# SupplyBox.net
KiCad netlist of a schematic drawn in Altium Designer
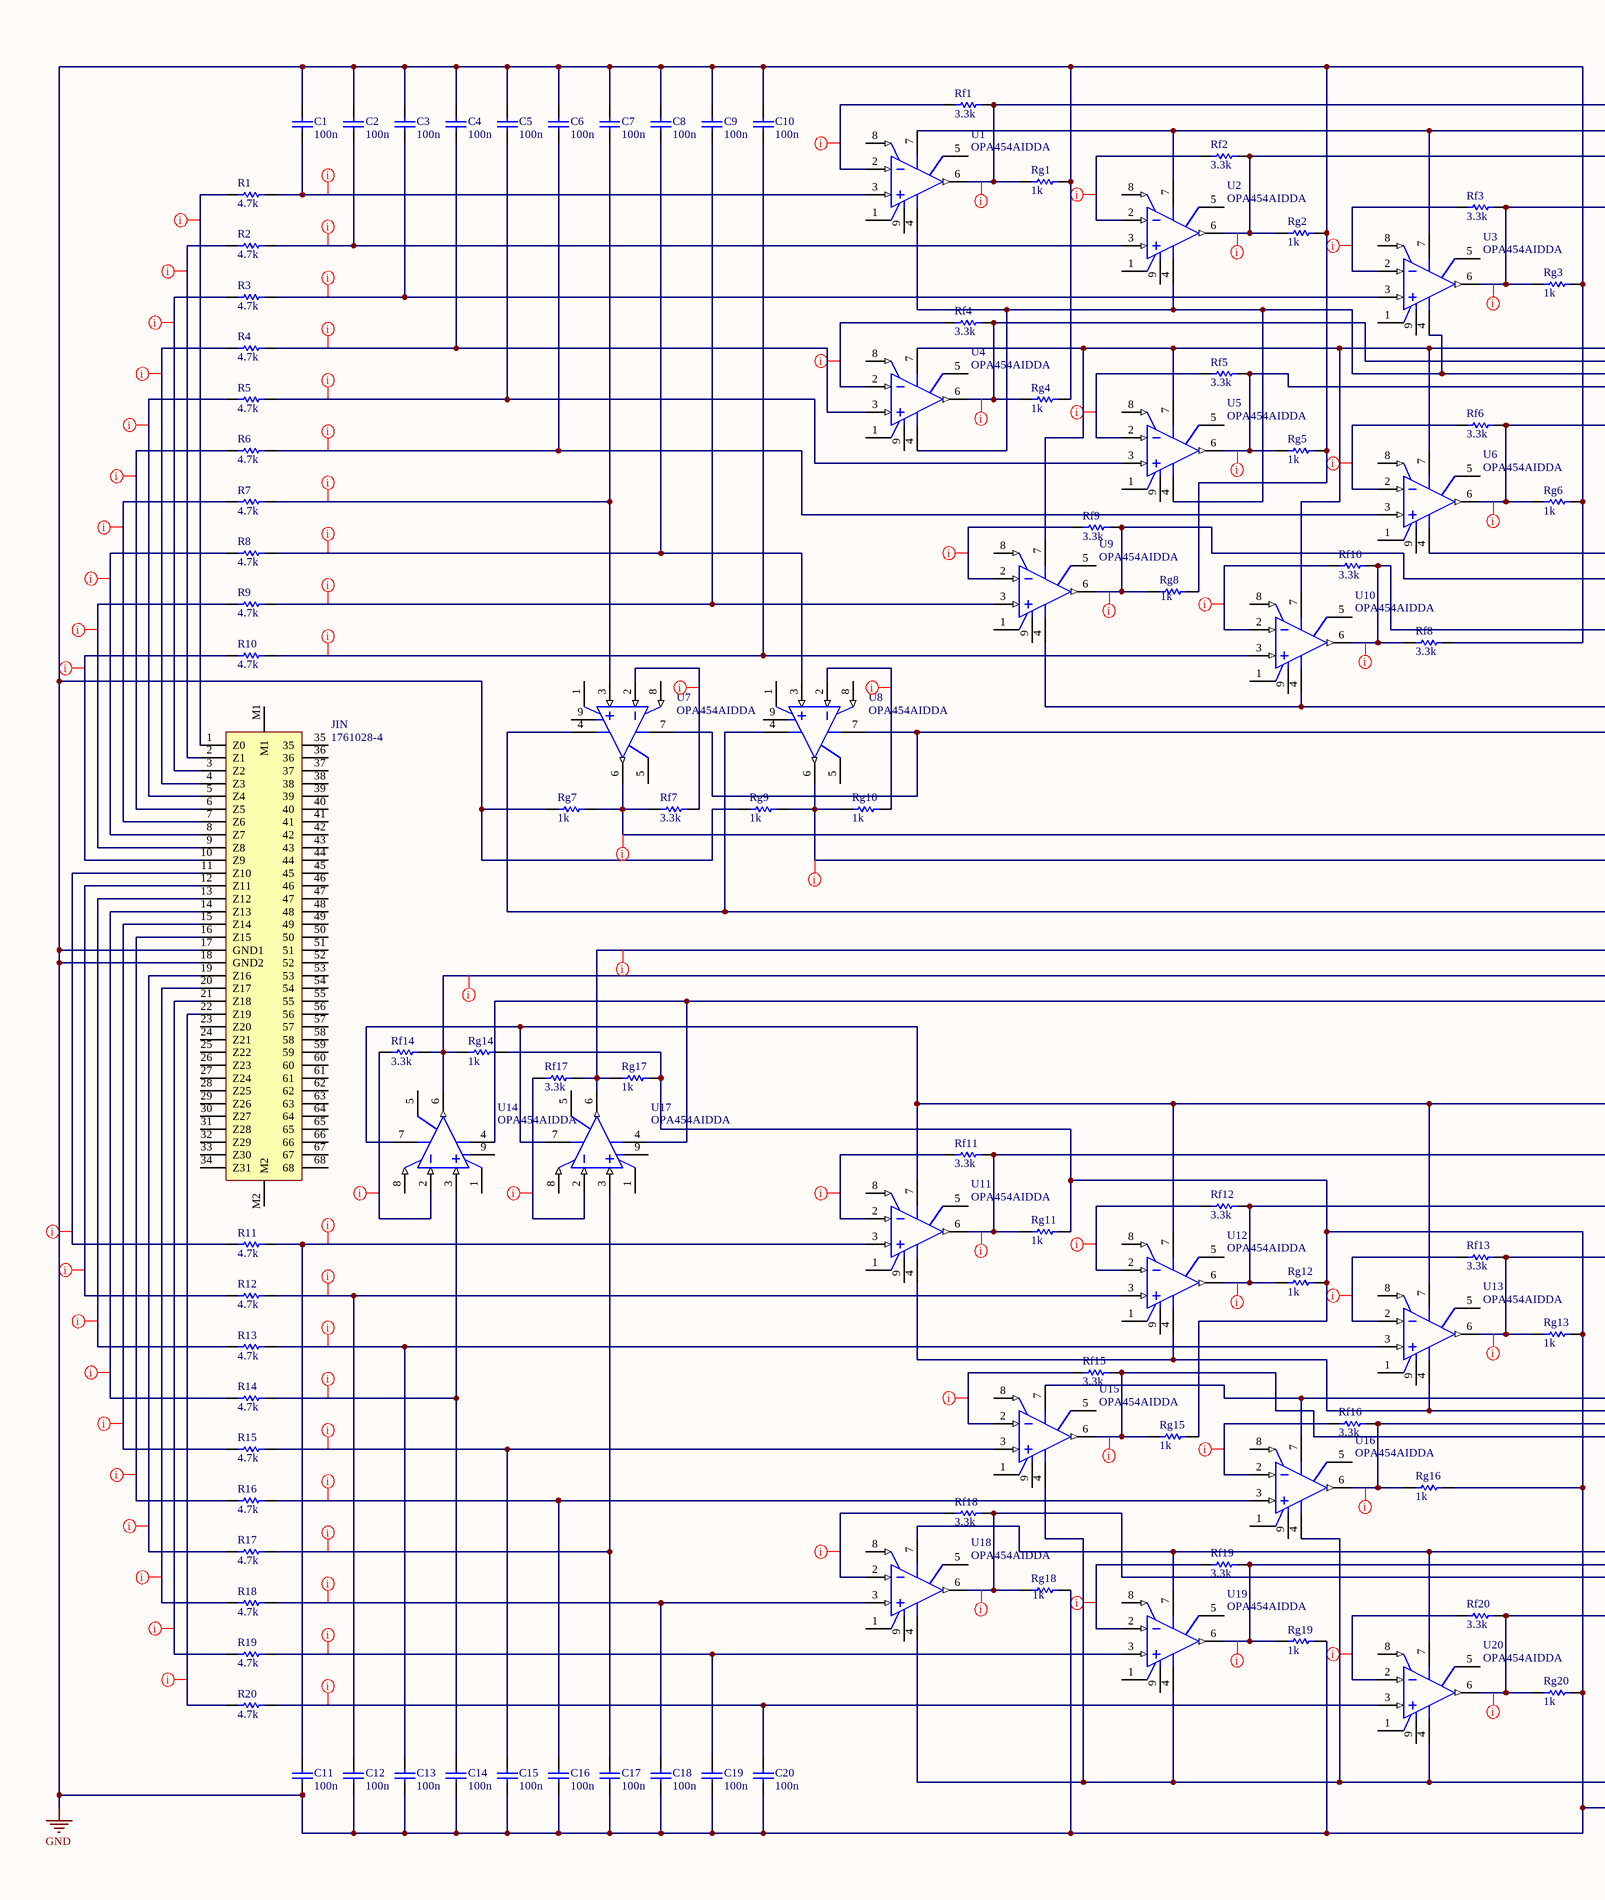
[diagram p0: SupplyBox.SchDoc, left]
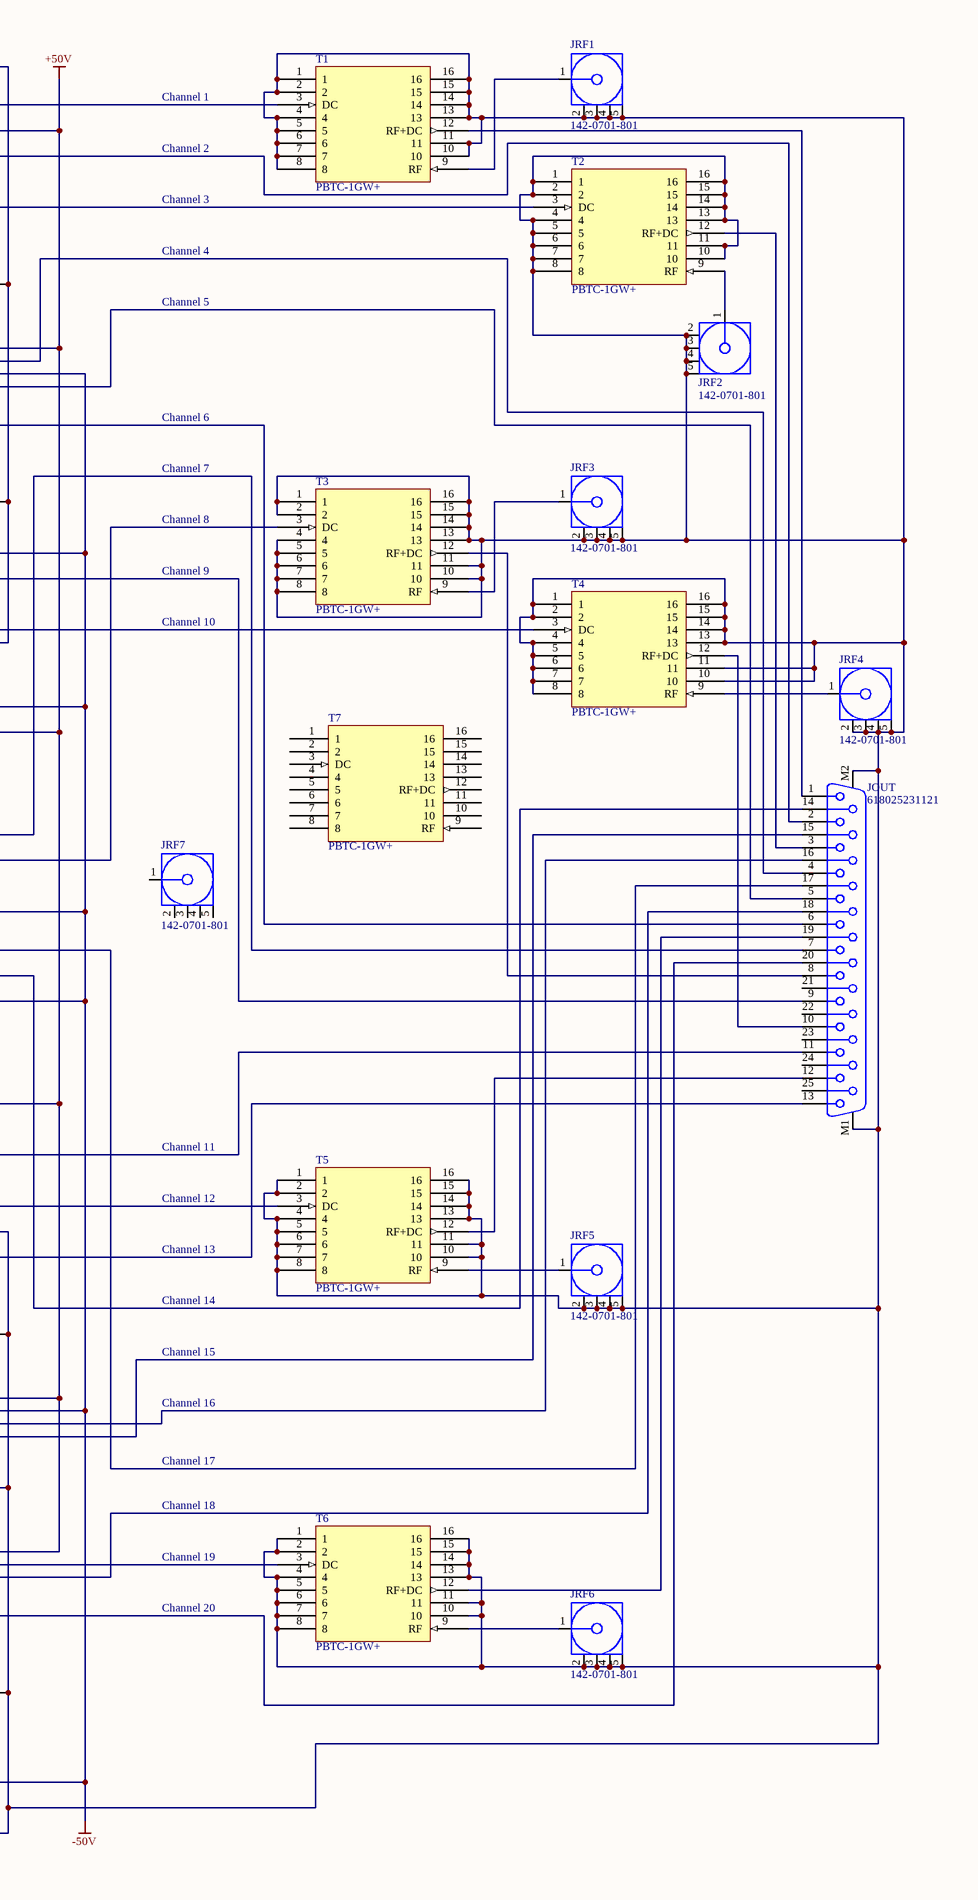
[diagram p1: SupplyBox.SchDoc, right]

(export (version "E")
  (design (tool "Eeschema 10.0.6"))
  (components
    (comp (ref "C1")
      (value "100n")
      (footprint "CAPC2013X145X48NL20T23")
      (fields (field (name "MANUFACTURER") "Vitramon") (field (name "PART NUMBER") "VJ0805Y104KNAAT"))
      (libsource (lib "Altium Content Vault") (part "CAP"))
    )
    (comp (ref "C2")
      (value "100n")
      (footprint "CAPC2013X145X48NL20T23")
      (fields (field (name "MANUFACTURER") "Vitramon") (field (name "PART NUMBER") "VJ0805Y104KNAAT"))
      (libsource (lib "Altium Content Vault") (part "CAP"))
    )
    (comp (ref "C3")
      (value "100n")
      (footprint "CAPC2013X145X48NL20T23")
      (fields (field (name "MANUFACTURER") "Vitramon") (field (name "PART NUMBER") "VJ0805Y104KNAAT"))
      (libsource (lib "Altium Content Vault") (part "CAP"))
    )
    (comp (ref "C4")
      (value "100n")
      (footprint "CAPC2013X145X48NL20T23")
      (fields (field (name "MANUFACTURER") "Vitramon") (field (name "PART NUMBER") "VJ0805Y104KNAAT"))
      (libsource (lib "Altium Content Vault") (part "CAP"))
    )
    (comp (ref "C5")
      (value "100n")
      (footprint "CAPC2013X145X48NL20T23")
      (fields (field (name "MANUFACTURER") "Vitramon") (field (name "PART NUMBER") "VJ0805Y104KNAAT"))
      (libsource (lib "Altium Content Vault") (part "CAP"))
    )
    (comp (ref "C6")
      (value "100n")
      (footprint "CAPC2013X145X48NL20T23")
      (fields (field (name "MANUFACTURER") "Vitramon") (field (name "PART NUMBER") "VJ0805Y104KNAAT"))
      (libsource (lib "Altium Content Vault") (part "CAP"))
    )
    (comp (ref "C7")
      (value "100n")
      (footprint "CAPC2013X145X48NL20T23")
      (fields (field (name "MANUFACTURER") "Vitramon") (field (name "PART NUMBER") "VJ0805Y104KNAAT"))
      (libsource (lib "Altium Content Vault") (part "CAP"))
    )
    (comp (ref "C8")
      (value "100n")
      (footprint "CAPC2013X145X48NL20T23")
      (fields (field (name "MANUFACTURER") "Vitramon") (field (name "PART NUMBER") "VJ0805Y104KNAAT"))
      (libsource (lib "Altium Content Vault") (part "CAP"))
    )
    (comp (ref "C9")
      (value "100n")
      (footprint "CAPC2013X145X48NL20T23")
      (fields (field (name "MANUFACTURER") "Vitramon") (field (name "PART NUMBER") "VJ0805Y104KNAAT"))
      (libsource (lib "Altium Content Vault") (part "CAP"))
    )
    (comp (ref "C10")
      (value "100n")
      (footprint "CAPC2013X145X48NL20T23")
      (fields (field (name "MANUFACTURER") "Vitramon") (field (name "PART NUMBER") "VJ0805Y104KNAAT"))
      (libsource (lib "Altium Content Vault") (part "CAP"))
    )
    (comp (ref "C11")
      (value "100n")
      (footprint "CAPC2013X145X48NL20T23")
      (fields (field (name "MANUFACTURER") "Vitramon") (field (name "PART NUMBER") "VJ0805Y104KNAAT"))
      (libsource (lib "Altium Content Vault") (part "CAP"))
    )
    (comp (ref "C12")
      (value "100n")
      (footprint "CAPC2013X145X48NL20T23")
      (fields (field (name "MANUFACTURER") "Vitramon") (field (name "PART NUMBER") "VJ0805Y104KNAAT"))
      (libsource (lib "Altium Content Vault") (part "CAP"))
    )
    (comp (ref "C13")
      (value "100n")
      (footprint "CAPC2013X145X48NL20T23")
      (fields (field (name "MANUFACTURER") "Vitramon") (field (name "PART NUMBER") "VJ0805Y104KNAAT"))
      (libsource (lib "Altium Content Vault") (part "CAP"))
    )
    (comp (ref "C14")
      (value "100n")
      (footprint "CAPC2013X145X48NL20T23")
      (fields (field (name "MANUFACTURER") "Vitramon") (field (name "PART NUMBER") "VJ0805Y104KNAAT"))
      (libsource (lib "Altium Content Vault") (part "CAP"))
    )
    (comp (ref "C15")
      (value "100n")
      (footprint "CAPC2013X145X48NL20T23")
      (fields (field (name "MANUFACTURER") "Vitramon") (field (name "PART NUMBER") "VJ0805Y104KNAAT"))
      (libsource (lib "Altium Content Vault") (part "CAP"))
    )
    (comp (ref "C16")
      (value "100n")
      (footprint "CAPC2013X145X48NL20T23")
      (fields (field (name "MANUFACTURER") "Vitramon") (field (name "PART NUMBER") "VJ0805Y104KNAAT"))
      (libsource (lib "Altium Content Vault") (part "CAP"))
    )
    (comp (ref "C17")
      (value "100n")
      (footprint "CAPC2013X145X48NL20T23")
      (fields (field (name "MANUFACTURER") "Vitramon") (field (name "PART NUMBER") "VJ0805Y104KNAAT"))
      (libsource (lib "Altium Content Vault") (part "CAP"))
    )
    (comp (ref "C18")
      (value "100n")
      (footprint "CAPC2013X145X48NL20T23")
      (fields (field (name "MANUFACTURER") "Vitramon") (field (name "PART NUMBER") "VJ0805Y104KNAAT"))
      (libsource (lib "Altium Content Vault") (part "CAP"))
    )
    (comp (ref "C19")
      (value "100n")
      (footprint "CAPC2013X145X48NL20T23")
      (fields (field (name "MANUFACTURER") "Vitramon") (field (name "PART NUMBER") "VJ0805Y104KNAAT"))
      (libsource (lib "Altium Content Vault") (part "CAP"))
    )
    (comp (ref "C20")
      (value "100n")
      (footprint "CAPC2013X145X48NL20T23")
      (fields (field (name "MANUFACTURER") "Vitramon") (field (name "PART NUMBER") "VJ0805Y104KNAAT"))
      (libsource (lib "Altium Content Vault") (part "CAP"))
    )
    (comp (ref "JIN")
      (value "1761028-4")
      (footprint "1761028-4-Footprint-1")
      (libsource (lib "Li-Ren Liu") (part "1761028-4-Symbol-1"))
    )
    (comp (ref "JOUT")
      (value "618025231121")
      (footprint "618025231121")
      (libsource (lib "Altium Content Vault") (part "D-Sub_Female_25p"))
    )
    (comp (ref "JRF1")
      (value "142-0701-801")
      (footprint "CINC-142-0701-801_V")
      (description "SMA End Launch Jack Receptacle, 50 Ohm, 0 to 18 GHz, -65 to 165 degC, 5-Pin SMD, RoHS, Bulk")
      (fields (field (name "MANUFACTURER") "EmersonConnectivitySolutions"))
      (libsource (lib "Altium Content Vault") (part "CN-S-4F-RF5"))
    )
    (comp (ref "JRF2")
      (value "142-0701-801")
      (footprint "CINC-142-0701-801_V")
      (description "SMA End Launch Jack Receptacle, 50 Ohm, 0 to 18 GHz, -65 to 165 degC, 5-Pin SMD, RoHS, Bulk")
      (fields (field (name "MANUFACTURER") "EmersonConnectivitySolutions"))
      (libsource (lib "Altium Content Vault") (part "CN-S-4F-RF5"))
    )
    (comp (ref "JRF3")
      (value "142-0701-801")
      (footprint "CINC-142-0701-801_V")
      (description "SMA End Launch Jack Receptacle, 50 Ohm, 0 to 18 GHz, -65 to 165 degC, 5-Pin SMD, RoHS, Bulk")
      (fields (field (name "MANUFACTURER") "EmersonConnectivitySolutions"))
      (libsource (lib "Altium Content Vault") (part "CN-S-4F-RF5"))
    )
    (comp (ref "JRF4")
      (value "142-0701-801")
      (footprint "CINC-142-0701-801_V")
      (description "SMA End Launch Jack Receptacle, 50 Ohm, 0 to 18 GHz, -65 to 165 degC, 5-Pin SMD, RoHS, Bulk")
      (fields (field (name "MANUFACTURER") "EmersonConnectivitySolutions"))
      (libsource (lib "Altium Content Vault") (part "CN-S-4F-RF5"))
    )
    (comp (ref "JRF5")
      (value "142-0701-801")
      (footprint "CINC-142-0701-801_V")
      (description "SMA End Launch Jack Receptacle, 50 Ohm, 0 to 18 GHz, -65 to 165 degC, 5-Pin SMD, RoHS, Bulk")
      (fields (field (name "MANUFACTURER") "EmersonConnectivitySolutions"))
      (libsource (lib "Altium Content Vault") (part "CN-S-4F-RF5"))
    )
    (comp (ref "JRF6")
      (value "142-0701-801")
      (footprint "CINC-142-0701-801_V")
      (description "SMA End Launch Jack Receptacle, 50 Ohm, 0 to 18 GHz, -65 to 165 degC, 5-Pin SMD, RoHS, Bulk")
      (fields (field (name "MANUFACTURER") "EmersonConnectivitySolutions"))
      (libsource (lib "Altium Content Vault") (part "CN-S-4F-RF5"))
    )
    (comp (ref "JRF7")
      (value "142-0701-801")
      (footprint "CINC-142-0701-801_V")
      (description "SMA End Launch Jack Receptacle, 50 Ohm, 0 to 18 GHz, -65 to 165 degC, 5-Pin SMD, RoHS, Bulk")
      (fields (field (name "MANUFACTURER") "EmersonConnectivitySolutions"))
      (libsource (lib "Altium Content Vault") (part "CN-S-4F-RF5"))
    )
    (comp (ref "R1")
      (value "4.7k")
      (footprint "RESC2013X60X35NL10T20")
      (description "Chip Resistor, 47 KOhm, +/- 1%, 0.125 W, -55 to 155 degC, 0805 (2012 Metric), RoHS, Tape and Reel")
      (fields (field (name "MANUFACTURER") "Yageo"))
      (libsource (lib "Altium Content Vault") (part "RES-2"))
    )
    (comp (ref "R2")
      (value "4.7k")
      (footprint "RESC2013X60X35NL10T20")
      (description "Chip Resistor, 47 KOhm, +/- 1%, 0.125 W, -55 to 155 degC, 0805 (2012 Metric), RoHS, Tape and Reel")
      (fields (field (name "MANUFACTURER") "Yageo"))
      (libsource (lib "Altium Content Vault") (part "RES-2"))
    )
    (comp (ref "R3")
      (value "4.7k")
      (footprint "RESC2013X60X35NL10T20")
      (description "Chip Resistor, 47 KOhm, +/- 1%, 0.125 W, -55 to 155 degC, 0805 (2012 Metric), RoHS, Tape and Reel")
      (fields (field (name "MANUFACTURER") "Yageo"))
      (libsource (lib "Altium Content Vault") (part "RES-2"))
    )
    (comp (ref "R4")
      (value "4.7k")
      (footprint "RESC2013X60X35NL10T20")
      (description "Chip Resistor, 47 KOhm, +/- 1%, 0.125 W, -55 to 155 degC, 0805 (2012 Metric), RoHS, Tape and Reel")
      (fields (field (name "MANUFACTURER") "Yageo"))
      (libsource (lib "Altium Content Vault") (part "RES-2"))
    )
    (comp (ref "R5")
      (value "4.7k")
      (footprint "RESC2013X60X35NL10T20")
      (description "Chip Resistor, 47 KOhm, +/- 1%, 0.125 W, -55 to 155 degC, 0805 (2012 Metric), RoHS, Tape and Reel")
      (fields (field (name "MANUFACTURER") "Yageo"))
      (libsource (lib "Altium Content Vault") (part "RES-2"))
    )
    (comp (ref "R6")
      (value "4.7k")
      (footprint "RESC2013X60X35NL10T20")
      (description "Chip Resistor, 47 KOhm, +/- 1%, 0.125 W, -55 to 155 degC, 0805 (2012 Metric), RoHS, Tape and Reel")
      (fields (field (name "MANUFACTURER") "Yageo"))
      (libsource (lib "Altium Content Vault") (part "RES-2"))
    )
    (comp (ref "R7")
      (value "4.7k")
      (footprint "RESC2013X60X35NL10T20")
      (description "Chip Resistor, 47 KOhm, +/- 1%, 0.125 W, -55 to 155 degC, 0805 (2012 Metric), RoHS, Tape and Reel")
      (fields (field (name "MANUFACTURER") "Yageo"))
      (libsource (lib "Altium Content Vault") (part "RES-2"))
    )
    (comp (ref "R8")
      (value "4.7k")
      (footprint "RESC2013X60X35NL10T20")
      (description "Chip Resistor, 47 KOhm, +/- 1%, 0.125 W, -55 to 155 degC, 0805 (2012 Metric), RoHS, Tape and Reel")
      (fields (field (name "MANUFACTURER") "Yageo"))
      (libsource (lib "Altium Content Vault") (part "RES-2"))
    )
    (comp (ref "R9")
      (value "4.7k")
      (footprint "RESC2013X60X35NL10T20")
      (description "Chip Resistor, 47 KOhm, +/- 1%, 0.125 W, -55 to 155 degC, 0805 (2012 Metric), RoHS, Tape and Reel")
      (fields (field (name "MANUFACTURER") "Yageo"))
      (libsource (lib "Altium Content Vault") (part "RES-2"))
    )
    (comp (ref "R10")
      (value "4.7k")
      (footprint "RESC2013X60X35NL10T20")
      (description "Chip Resistor, 47 KOhm, +/- 1%, 0.125 W, -55 to 155 degC, 0805 (2012 Metric), RoHS, Tape and Reel")
      (fields (field (name "MANUFACTURER") "Yageo"))
      (libsource (lib "Altium Content Vault") (part "RES-2"))
    )
    (comp (ref "R11")
      (value "4.7k")
      (footprint "RESC2013X60X35NL10T20")
      (description "Chip Resistor, 47 KOhm, +/- 1%, 0.125 W, -55 to 155 degC, 0805 (2012 Metric), RoHS, Tape and Reel")
      (fields (field (name "MANUFACTURER") "Yageo"))
      (libsource (lib "Altium Content Vault") (part "RES-2"))
    )
    (comp (ref "R12")
      (value "4.7k")
      (footprint "RESC2013X60X35NL10T20")
      (description "Chip Resistor, 47 KOhm, +/- 1%, 0.125 W, -55 to 155 degC, 0805 (2012 Metric), RoHS, Tape and Reel")
      (fields (field (name "MANUFACTURER") "Yageo"))
      (libsource (lib "Altium Content Vault") (part "RES-2"))
    )
    (comp (ref "R13")
      (value "4.7k")
      (footprint "RESC2013X60X35NL10T20")
      (description "Chip Resistor, 47 KOhm, +/- 1%, 0.125 W, -55 to 155 degC, 0805 (2012 Metric), RoHS, Tape and Reel")
      (fields (field (name "MANUFACTURER") "Yageo"))
      (libsource (lib "Altium Content Vault") (part "RES-2"))
    )
    (comp (ref "R14")
      (value "4.7k")
      (footprint "RESC2013X60X35NL10T20")
      (description "Chip Resistor, 47 KOhm, +/- 1%, 0.125 W, -55 to 155 degC, 0805 (2012 Metric), RoHS, Tape and Reel")
      (fields (field (name "MANUFACTURER") "Yageo"))
      (libsource (lib "Altium Content Vault") (part "RES-2"))
    )
    (comp (ref "R15")
      (value "4.7k")
      (footprint "RESC2013X60X35NL10T20")
      (description "Chip Resistor, 47 KOhm, +/- 1%, 0.125 W, -55 to 155 degC, 0805 (2012 Metric), RoHS, Tape and Reel")
      (fields (field (name "MANUFACTURER") "Yageo"))
      (libsource (lib "Altium Content Vault") (part "RES-2"))
    )
    (comp (ref "R16")
      (value "4.7k")
      (footprint "RESC2013X60X35NL10T20")
      (description "Chip Resistor, 47 KOhm, +/- 1%, 0.125 W, -55 to 155 degC, 0805 (2012 Metric), RoHS, Tape and Reel")
      (fields (field (name "MANUFACTURER") "Yageo"))
      (libsource (lib "Altium Content Vault") (part "RES-2"))
    )
    (comp (ref "R17")
      (value "4.7k")
      (footprint "RESC2013X60X35NL10T20")
      (description "Chip Resistor, 47 KOhm, +/- 1%, 0.125 W, -55 to 155 degC, 0805 (2012 Metric), RoHS, Tape and Reel")
      (fields (field (name "MANUFACTURER") "Yageo"))
      (libsource (lib "Altium Content Vault") (part "RES-2"))
    )
    (comp (ref "R18")
      (value "4.7k")
      (footprint "RESC2013X60X35NL10T20")
      (description "Chip Resistor, 47 KOhm, +/- 1%, 0.125 W, -55 to 155 degC, 0805 (2012 Metric), RoHS, Tape and Reel")
      (fields (field (name "MANUFACTURER") "Yageo"))
      (libsource (lib "Altium Content Vault") (part "RES-2"))
    )
    (comp (ref "R19")
      (value "4.7k")
      (footprint "RESC2013X60X35NL10T20")
      (description "Chip Resistor, 47 KOhm, +/- 1%, 0.125 W, -55 to 155 degC, 0805 (2012 Metric), RoHS, Tape and Reel")
      (fields (field (name "MANUFACTURER") "Yageo"))
      (libsource (lib "Altium Content Vault") (part "RES-2"))
    )
    (comp (ref "R20")
      (value "4.7k")
      (footprint "RESC2013X60X35NL10T20")
      (description "Chip Resistor, 47 KOhm, +/- 1%, 0.125 W, -55 to 155 degC, 0805 (2012 Metric), RoHS, Tape and Reel")
      (fields (field (name "MANUFACTURER") "Yageo"))
      (libsource (lib "Altium Content Vault") (part "RES-2"))
    )
    (comp (ref "Rf1")
      (value "3.3k")
      (footprint "RESC2013X60X35ML10T20")
      (description "Chip Resistor, 3.3 KOhm, +/- 1%, 0.125 W, -55 to 155 degC, 0805 (2012 Metric), RoHS, Tape and Reel")
      (fields (field (name "TOLERANCE") "1%") (field (name "MANUFACTURER") "Yageo"))
      (libsource (lib "Altium Content Vault") (part "RES-2"))
    )
    (comp (ref "Rf2")
      (value "3.3k")
      (footprint "RESC2013X60X35ML10T20")
      (description "Chip Resistor, 3.3 KOhm, +/- 1%, 0.125 W, -55 to 155 degC, 0805 (2012 Metric), RoHS, Tape and Reel")
      (fields (field (name "TOLERANCE") "1%") (field (name "MANUFACTURER") "Yageo"))
      (libsource (lib "Altium Content Vault") (part "RES-2"))
    )
    (comp (ref "Rf3")
      (value "3.3k")
      (footprint "RESC2013X60X35ML10T20")
      (description "Chip Resistor, 3.3 KOhm, +/- 1%, 0.125 W, -55 to 155 degC, 0805 (2012 Metric), RoHS, Tape and Reel")
      (fields (field (name "TOLERANCE") "1%") (field (name "MANUFACTURER") "Yageo"))
      (libsource (lib "Altium Content Vault") (part "RES-2"))
    )
    (comp (ref "Rf4")
      (value "3.3k")
      (footprint "RESC2013X60X35ML10T20")
      (description "Chip Resistor, 3.3 KOhm, +/- 1%, 0.125 W, -55 to 155 degC, 0805 (2012 Metric), RoHS, Tape and Reel")
      (fields (field (name "TOLERANCE") "1%") (field (name "MANUFACTURER") "Yageo"))
      (libsource (lib "Altium Content Vault") (part "RES-2"))
    )
    (comp (ref "Rf5")
      (value "3.3k")
      (footprint "RESC2013X60X35ML10T20")
      (description "Chip Resistor, 3.3 KOhm, +/- 1%, 0.125 W, -55 to 155 degC, 0805 (2012 Metric), RoHS, Tape and Reel")
      (fields (field (name "TOLERANCE") "1%") (field (name "MANUFACTURER") "Yageo"))
      (libsource (lib "Altium Content Vault") (part "RES-2"))
    )
    (comp (ref "Rf6")
      (value "3.3k")
      (footprint "RESC2013X60X35ML10T20")
      (description "Chip Resistor, 3.3 KOhm, +/- 1%, 0.125 W, -55 to 155 degC, 0805 (2012 Metric), RoHS, Tape and Reel")
      (fields (field (name "TOLERANCE") "1%") (field (name "MANUFACTURER") "Yageo"))
      (libsource (lib "Altium Content Vault") (part "RES-2"))
    )
    (comp (ref "Rf7")
      (value "3.3k")
      (footprint "RESC2013X60X35ML10T20")
      (description "Chip Resistor, 3.3 KOhm, +/- 1%, 0.125 W, -55 to 155 degC, 0805 (2012 Metric), RoHS, Tape and Reel")
      (fields (field (name "TOLERANCE") "1%") (field (name "MANUFACTURER") "Yageo"))
      (libsource (lib "Altium Content Vault") (part "RES-2"))
    )
    (comp (ref "Rf8")
      (value "3.3k")
      (footprint "RESC2013X60X35ML10T20")
      (description "Chip Resistor, 3.3 KOhm, +/- 1%, 0.125 W, -55 to 155 degC, 0805 (2012 Metric), RoHS, Tape and Reel")
      (fields (field (name "TOLERANCE") "1%") (field (name "MANUFACTURER") "Yageo"))
      (libsource (lib "Altium Content Vault") (part "RES-2"))
    )
    (comp (ref "Rf9")
      (value "3.3k")
      (footprint "RESC2013X60X35ML10T20")
      (description "Chip Resistor, 3.3 KOhm, +/- 1%, 0.125 W, -55 to 155 degC, 0805 (2012 Metric), RoHS, Tape and Reel")
      (fields (field (name "TOLERANCE") "1%") (field (name "MANUFACTURER") "Yageo"))
      (libsource (lib "Altium Content Vault") (part "RES-2"))
    )
    (comp (ref "Rf10")
      (value "3.3k")
      (footprint "RESC2013X60X35ML10T20")
      (description "Chip Resistor, 3.3 KOhm, +/- 1%, 0.125 W, -55 to 155 degC, 0805 (2012 Metric), RoHS, Tape and Reel")
      (fields (field (name "TOLERANCE") "1%") (field (name "MANUFACTURER") "Yageo"))
      (libsource (lib "Altium Content Vault") (part "RES-2"))
    )
    (comp (ref "Rf11")
      (value "3.3k")
      (footprint "RESC2013X60X35ML10T20")
      (description "Chip Resistor, 3.3 KOhm, +/- 1%, 0.125 W, -55 to 155 degC, 0805 (2012 Metric), RoHS, Tape and Reel")
      (fields (field (name "TOLERANCE") "1%") (field (name "MANUFACTURER") "Yageo"))
      (libsource (lib "Altium Content Vault") (part "RES-2"))
    )
    (comp (ref "Rf12")
      (value "3.3k")
      (footprint "RESC2013X60X35ML10T20")
      (description "Chip Resistor, 3.3 KOhm, +/- 1%, 0.125 W, -55 to 155 degC, 0805 (2012 Metric), RoHS, Tape and Reel")
      (fields (field (name "TOLERANCE") "1%") (field (name "MANUFACTURER") "Yageo"))
      (libsource (lib "Altium Content Vault") (part "RES-2"))
    )
    (comp (ref "Rf13")
      (value "3.3k")
      (footprint "RESC2013X60X35ML10T20")
      (description "Chip Resistor, 3.3 KOhm, +/- 1%, 0.125 W, -55 to 155 degC, 0805 (2012 Metric), RoHS, Tape and Reel")
      (fields (field (name "TOLERANCE") "1%") (field (name "MANUFACTURER") "Yageo"))
      (libsource (lib "Altium Content Vault") (part "RES-2"))
    )
    (comp (ref "Rf14")
      (value "3.3k")
      (footprint "RESC2013X60X35ML10T20")
      (description "Chip Resistor, 3.3 KOhm, +/- 1%, 0.125 W, -55 to 155 degC, 0805 (2012 Metric), RoHS, Tape and Reel")
      (fields (field (name "TOLERANCE") "1%") (field (name "MANUFACTURER") "Yageo"))
      (libsource (lib "Altium Content Vault") (part "RES-2"))
    )
    (comp (ref "Rf15")
      (value "3.3k")
      (footprint "RESC2013X60X35ML10T20")
      (description "Chip Resistor, 3.3 KOhm, +/- 1%, 0.125 W, -55 to 155 degC, 0805 (2012 Metric), RoHS, Tape and Reel")
      (fields (field (name "TOLERANCE") "1%") (field (name "MANUFACTURER") "Yageo"))
      (libsource (lib "Altium Content Vault") (part "RES-2"))
    )
    (comp (ref "Rf16")
      (value "3.3k")
      (footprint "RESC2013X60X35ML10T20")
      (description "Chip Resistor, 3.3 KOhm, +/- 1%, 0.125 W, -55 to 155 degC, 0805 (2012 Metric), RoHS, Tape and Reel")
      (fields (field (name "TOLERANCE") "1%") (field (name "MANUFACTURER") "Yageo"))
      (libsource (lib "Altium Content Vault") (part "RES-2"))
    )
    (comp (ref "Rf17")
      (value "3.3k")
      (footprint "RESC2013X60X35ML10T20")
      (description "Chip Resistor, 3.3 KOhm, +/- 1%, 0.125 W, -55 to 155 degC, 0805 (2012 Metric), RoHS, Tape and Reel")
      (fields (field (name "TOLERANCE") "1%") (field (name "MANUFACTURER") "Yageo"))
      (libsource (lib "Altium Content Vault") (part "RES-2"))
    )
    (comp (ref "Rf18")
      (value "3.3k")
      (footprint "RESC2013X60X35ML10T20")
      (description "Chip Resistor, 3.3 KOhm, +/- 1%, 0.125 W, -55 to 155 degC, 0805 (2012 Metric), RoHS, Tape and Reel")
      (fields (field (name "TOLERANCE") "1%") (field (name "MANUFACTURER") "Yageo"))
      (libsource (lib "Altium Content Vault") (part "RES-2"))
    )
    (comp (ref "Rf19")
      (value "3.3k")
      (footprint "RESC2013X60X35ML10T20")
      (description "Chip Resistor, 3.3 KOhm, +/- 1%, 0.125 W, -55 to 155 degC, 0805 (2012 Metric), RoHS, Tape and Reel")
      (fields (field (name "TOLERANCE") "1%") (field (name "MANUFACTURER") "Yageo"))
      (libsource (lib "Altium Content Vault") (part "RES-2"))
    )
    (comp (ref "Rf20")
      (value "3.3k")
      (footprint "RESC2013X60X35ML10T20")
      (description "Chip Resistor, 3.3 KOhm, +/- 1%, 0.125 W, -55 to 155 degC, 0805 (2012 Metric), RoHS, Tape and Reel")
      (fields (field (name "TOLERANCE") "1%") (field (name "MANUFACTURER") "Yageo"))
      (libsource (lib "Altium Content Vault") (part "RES-2"))
    )
    (comp (ref "Rg1")
      (value "1k")
      (footprint "RESC2013X60X35ML10T20")
      (description "Chip Resistor, 1 KOhm, +/- 1%, 125 mW, -55 to 155 degC, 0805 (2012 Metric), RoHS, Tape and Reel")
      (fields (field (name "TOLERANCE") "1%") (field (name "MANUFACTURER") "Yageo"))
      (libsource (lib "Altium Content Vault") (part "RES-2"))
    )
    (comp (ref "Rg2")
      (value "1k")
      (footprint "RESC2013X60X35ML10T20")
      (description "Chip Resistor, 1 KOhm, +/- 1%, 125 mW, -55 to 155 degC, 0805 (2012 Metric), RoHS, Tape and Reel")
      (fields (field (name "TOLERANCE") "1%") (field (name "MANUFACTURER") "Yageo"))
      (libsource (lib "Altium Content Vault") (part "RES-2"))
    )
    (comp (ref "Rg3")
      (value "1k")
      (footprint "RESC2013X60X35ML10T20")
      (description "Chip Resistor, 1 KOhm, +/- 1%, 125 mW, -55 to 155 degC, 0805 (2012 Metric), RoHS, Tape and Reel")
      (fields (field (name "TOLERANCE") "1%") (field (name "MANUFACTURER") "Yageo"))
      (libsource (lib "Altium Content Vault") (part "RES-2"))
    )
    (comp (ref "Rg4")
      (value "1k")
      (footprint "RESC2013X60X35ML10T20")
      (description "Chip Resistor, 1 KOhm, +/- 1%, 125 mW, -55 to 155 degC, 0805 (2012 Metric), RoHS, Tape and Reel")
      (fields (field (name "TOLERANCE") "1%") (field (name "MANUFACTURER") "Yageo"))
      (libsource (lib "Altium Content Vault") (part "RES-2"))
    )
    (comp (ref "Rg5")
      (value "1k")
      (footprint "RESC2013X60X35ML10T20")
      (description "Chip Resistor, 1 KOhm, +/- 1%, 125 mW, -55 to 155 degC, 0805 (2012 Metric), RoHS, Tape and Reel")
      (fields (field (name "TOLERANCE") "1%") (field (name "MANUFACTURER") "Yageo"))
      (libsource (lib "Altium Content Vault") (part "RES-2"))
    )
    (comp (ref "Rg6")
      (value "1k")
      (footprint "RESC2013X60X35ML10T20")
      (description "Chip Resistor, 1 KOhm, +/- 1%, 125 mW, -55 to 155 degC, 0805 (2012 Metric), RoHS, Tape and Reel")
      (fields (field (name "TOLERANCE") "1%") (field (name "MANUFACTURER") "Yageo"))
      (libsource (lib "Altium Content Vault") (part "RES-2"))
    )
    (comp (ref "Rg7")
      (value "1k")
      (footprint "RESC2013X60X35ML10T20")
      (description "Chip Resistor, 1 KOhm, +/- 1%, 125 mW, -55 to 155 degC, 0805 (2012 Metric), RoHS, Tape and Reel")
      (fields (field (name "TOLERANCE") "1%") (field (name "MANUFACTURER") "Yageo"))
      (libsource (lib "Altium Content Vault") (part "RES-2"))
    )
    (comp (ref "Rg8")
      (value "1k")
      (footprint "RESC2013X60X35ML10T20")
      (description "Chip Resistor, 1 KOhm, +/- 1%, 125 mW, -55 to 155 degC, 0805 (2012 Metric), RoHS, Tape and Reel")
      (fields (field (name "TOLERANCE") "1%") (field (name "MANUFACTURER") "Yageo"))
      (libsource (lib "Altium Content Vault") (part "RES-2"))
    )
    (comp (ref "Rg9")
      (value "1k")
      (footprint "RESC2013X60X35ML10T20")
      (description "Chip Resistor, 1 KOhm, +/- 1%, 125 mW, -55 to 155 degC, 0805 (2012 Metric), RoHS, Tape and Reel")
      (fields (field (name "TOLERANCE") "1%") (field (name "MANUFACTURER") "Yageo"))
      (libsource (lib "Altium Content Vault") (part "RES-2"))
    )
    (comp (ref "Rg10")
      (value "1k")
      (footprint "RESC2013X60X35ML10T20")
      (description "Chip Resistor, 1 KOhm, +/- 1%, 125 mW, -55 to 155 degC, 0805 (2012 Metric), RoHS, Tape and Reel")
      (fields (field (name "TOLERANCE") "1%") (field (name "MANUFACTURER") "Yageo"))
      (libsource (lib "Altium Content Vault") (part "RES-2"))
    )
    (comp (ref "Rg11")
      (value "1k")
      (footprint "RESC2013X60X35ML10T20")
      (description "Chip Resistor, 1 KOhm, +/- 1%, 125 mW, -55 to 155 degC, 0805 (2012 Metric), RoHS, Tape and Reel")
      (fields (field (name "TOLERANCE") "1%") (field (name "MANUFACTURER") "Yageo"))
      (libsource (lib "Altium Content Vault") (part "RES-2"))
    )
    (comp (ref "Rg12")
      (value "1k")
      (footprint "RESC2013X60X35ML10T20")
      (description "Chip Resistor, 1 KOhm, +/- 1%, 125 mW, -55 to 155 degC, 0805 (2012 Metric), RoHS, Tape and Reel")
      (fields (field (name "TOLERANCE") "1%") (field (name "MANUFACTURER") "Yageo"))
      (libsource (lib "Altium Content Vault") (part "RES-2"))
    )
    (comp (ref "Rg13")
      (value "1k")
      (footprint "RESC2013X60X35ML10T20")
      (description "Chip Resistor, 1 KOhm, +/- 1%, 125 mW, -55 to 155 degC, 0805 (2012 Metric), RoHS, Tape and Reel")
      (fields (field (name "TOLERANCE") "1%") (field (name "MANUFACTURER") "Yageo"))
      (libsource (lib "Altium Content Vault") (part "RES-2"))
    )
    (comp (ref "Rg14")
      (value "1k")
      (footprint "RESC2013X60X35ML10T20")
      (description "Chip Resistor, 1 KOhm, +/- 1%, 125 mW, -55 to 155 degC, 0805 (2012 Metric), RoHS, Tape and Reel")
      (fields (field (name "TOLERANCE") "1%") (field (name "MANUFACTURER") "Yageo"))
      (libsource (lib "Altium Content Vault") (part "RES-2"))
    )
    (comp (ref "Rg15")
      (value "1k")
      (footprint "RESC2013X60X35ML10T20")
      (description "Chip Resistor, 1 KOhm, +/- 1%, 125 mW, -55 to 155 degC, 0805 (2012 Metric), RoHS, Tape and Reel")
      (fields (field (name "TOLERANCE") "1%") (field (name "MANUFACTURER") "Yageo"))
      (libsource (lib "Altium Content Vault") (part "RES-2"))
    )
    (comp (ref "Rg16")
      (value "1k")
      (footprint "RESC2013X60X35ML10T20")
      (description "Chip Resistor, 1 KOhm, +/- 1%, 125 mW, -55 to 155 degC, 0805 (2012 Metric), RoHS, Tape and Reel")
      (fields (field (name "TOLERANCE") "1%") (field (name "MANUFACTURER") "Yageo"))
      (libsource (lib "Altium Content Vault") (part "RES-2"))
    )
    (comp (ref "Rg17")
      (value "1k")
      (footprint "RESC2013X60X35ML10T20")
      (description "Chip Resistor, 1 KOhm, +/- 1%, 125 mW, -55 to 155 degC, 0805 (2012 Metric), RoHS, Tape and Reel")
      (fields (field (name "TOLERANCE") "1%") (field (name "MANUFACTURER") "Yageo"))
      (libsource (lib "Altium Content Vault") (part "RES-2"))
    )
    (comp (ref "Rg18")
      (value "1k")
      (footprint "RESC2013X60X35ML10T20")
      (description "Chip Resistor, 1 KOhm, +/- 1%, 125 mW, -55 to 155 degC, 0805 (2012 Metric), RoHS, Tape and Reel")
      (fields (field (name "TOLERANCE") "1%") (field (name "MANUFACTURER") "Yageo"))
      (libsource (lib "Altium Content Vault") (part "RES-2"))
    )
    (comp (ref "Rg19")
      (value "1k")
      (footprint "RESC2013X60X35ML10T20")
      (description "Chip Resistor, 1 KOhm, +/- 1%, 125 mW, -55 to 155 degC, 0805 (2012 Metric), RoHS, Tape and Reel")
      (fields (field (name "TOLERANCE") "1%") (field (name "MANUFACTURER") "Yageo"))
      (libsource (lib "Altium Content Vault") (part "RES-2"))
    )
    (comp (ref "Rg20")
      (value "1k")
      (footprint "RESC2013X60X35ML10T20")
      (description "Chip Resistor, 1 KOhm, +/- 1%, 125 mW, -55 to 155 degC, 0805 (2012 Metric), RoHS, Tape and Reel")
      (fields (field (name "TOLERANCE") "1%") (field (name "MANUFACTURER") "Yageo"))
      (libsource (lib "Altium Content Vault") (part "RES-2"))
    )
    (comp (ref "T1")
      (value "PBTC-1GW+")
      (footprint "PBTC-1GW+")
      (description "Monitor TEE DC Block, 0.1MHz Min, 1000MHz Max, 1dB Insertion Loss-Max")
      (libsource (lib "Li-Ren Liu") (part "PBTC-1GW+-Symbol-1"))
    )
    (comp (ref "T2")
      (value "PBTC-1GW+")
      (footprint "PBTC-1GW+")
      (description "Monitor TEE DC Block, 0.1MHz Min, 1000MHz Max, 1dB Insertion Loss-Max")
      (libsource (lib "Li-Ren Liu") (part "PBTC-1GW+-Symbol-1"))
    )
    (comp (ref "T3")
      (value "PBTC-1GW+")
      (footprint "PBTC-1GW+")
      (description "Monitor TEE DC Block, 0.1MHz Min, 1000MHz Max, 1dB Insertion Loss-Max")
      (libsource (lib "Li-Ren Liu") (part "PBTC-1GW+-Symbol-1"))
    )
    (comp (ref "T4")
      (value "PBTC-1GW+")
      (footprint "PBTC-1GW+")
      (description "Monitor TEE DC Block, 0.1MHz Min, 1000MHz Max, 1dB Insertion Loss-Max")
      (libsource (lib "Li-Ren Liu") (part "PBTC-1GW+-Symbol-1"))
    )
    (comp (ref "T5")
      (value "PBTC-1GW+")
      (footprint "PBTC-1GW+")
      (description "Monitor TEE DC Block, 0.1MHz Min, 1000MHz Max, 1dB Insertion Loss-Max")
      (libsource (lib "Li-Ren Liu") (part "PBTC-1GW+-Symbol-1"))
    )
    (comp (ref "T6")
      (value "PBTC-1GW+")
      (footprint "PBTC-1GW+")
      (description "Monitor TEE DC Block, 0.1MHz Min, 1000MHz Max, 1dB Insertion Loss-Max")
      (libsource (lib "Li-Ren Liu") (part "PBTC-1GW+-Symbol-1"))
    )
    (comp (ref "T7")
      (value "PBTC-1GW+")
      (footprint "PBTC-1GW+")
      (description "Monitor TEE DC Block, 0.1MHz Min, 1000MHz Max, 1dB Insertion Loss-Max")
      (libsource (lib "Li-Ren Liu") (part "PBTC-1GW+-Symbol-1"))
    )
    (comp (ref "U1")
      (value "OPA454AIDDA")
      (footprint "DDA0008C_L")
      (fields (field (name "MANUFACTURER") "Texas Instruments"))
      (libsource (lib "Altium Content Vault") (part "TI-OPA454-DDA8"))
    )
    (comp (ref "U2")
      (value "OPA454AIDDA")
      (footprint "DDA0008C_L")
      (fields (field (name "MANUFACTURER") "Texas Instruments"))
      (libsource (lib "Altium Content Vault") (part "TI-OPA454-DDA8"))
    )
    (comp (ref "U3")
      (value "OPA454AIDDA")
      (footprint "DDA0008C_L")
      (fields (field (name "MANUFACTURER") "Texas Instruments"))
      (libsource (lib "Altium Content Vault") (part "TI-OPA454-DDA8"))
    )
    (comp (ref "U4")
      (value "OPA454AIDDA")
      (footprint "DDA0008C_L")
      (fields (field (name "MANUFACTURER") "Texas Instruments"))
      (libsource (lib "Altium Content Vault") (part "TI-OPA454-DDA8"))
    )
    (comp (ref "U5")
      (value "OPA454AIDDA")
      (footprint "DDA0008C_L")
      (fields (field (name "MANUFACTURER") "Texas Instruments"))
      (libsource (lib "Altium Content Vault") (part "TI-OPA454-DDA8"))
    )
    (comp (ref "U6")
      (value "OPA454AIDDA")
      (footprint "DDA0008C_L")
      (fields (field (name "MANUFACTURER") "Texas Instruments"))
      (libsource (lib "Altium Content Vault") (part "TI-OPA454-DDA8"))
    )
    (comp (ref "U7")
      (value "OPA454AIDDA")
      (footprint "DDA0008C_L")
      (fields (field (name "MANUFACTURER") "Texas Instruments"))
      (libsource (lib "Altium Content Vault") (part "TI-OPA454-DDA8"))
    )
    (comp (ref "U8")
      (value "OPA454AIDDA")
      (footprint "DDA0008C_L")
      (fields (field (name "MANUFACTURER") "Texas Instruments"))
      (libsource (lib "Altium Content Vault") (part "TI-OPA454-DDA8"))
    )
    (comp (ref "U9")
      (value "OPA454AIDDA")
      (footprint "DDA0008C_L")
      (fields (field (name "MANUFACTURER") "Texas Instruments"))
      (libsource (lib "Altium Content Vault") (part "TI-OPA454-DDA8"))
    )
    (comp (ref "U10")
      (value "OPA454AIDDA")
      (footprint "DDA0008C_L")
      (fields (field (name "MANUFACTURER") "Texas Instruments"))
      (libsource (lib "Altium Content Vault") (part "TI-OPA454-DDA8"))
    )
    (comp (ref "U11")
      (value "OPA454AIDDA")
      (footprint "DDA0008C_L")
      (fields (field (name "MANUFACTURER") "Texas Instruments"))
      (libsource (lib "Altium Content Vault") (part "TI-OPA454-DDA8"))
    )
    (comp (ref "U12")
      (value "OPA454AIDDA")
      (footprint "DDA0008C_L")
      (fields (field (name "MANUFACTURER") "Texas Instruments"))
      (libsource (lib "Altium Content Vault") (part "TI-OPA454-DDA8"))
    )
    (comp (ref "U13")
      (value "OPA454AIDDA")
      (footprint "DDA0008C_L")
      (fields (field (name "MANUFACTURER") "Texas Instruments"))
      (libsource (lib "Altium Content Vault") (part "TI-OPA454-DDA8"))
    )
    (comp (ref "U14")
      (value "OPA454AIDDA")
      (footprint "DDA0008C_L")
      (fields (field (name "MANUFACTURER") "Texas Instruments"))
      (libsource (lib "Altium Content Vault") (part "TI-OPA454-DDA8"))
    )
    (comp (ref "U15")
      (value "OPA454AIDDA")
      (footprint "DDA0008C_L")
      (fields (field (name "MANUFACTURER") "Texas Instruments"))
      (libsource (lib "Altium Content Vault") (part "TI-OPA454-DDA8"))
    )
    (comp (ref "U16")
      (value "OPA454AIDDA")
      (footprint "DDA0008C_L")
      (fields (field (name "MANUFACTURER") "Texas Instruments"))
      (libsource (lib "Altium Content Vault") (part "TI-OPA454-DDA8"))
    )
    (comp (ref "U17")
      (value "OPA454AIDDA")
      (footprint "DDA0008C_L")
      (fields (field (name "MANUFACTURER") "Texas Instruments"))
      (libsource (lib "Altium Content Vault") (part "TI-OPA454-DDA8"))
    )
    (comp (ref "U18")
      (value "OPA454AIDDA")
      (footprint "DDA0008C_L")
      (fields (field (name "MANUFACTURER") "Texas Instruments"))
      (libsource (lib "Altium Content Vault") (part "TI-OPA454-DDA8"))
    )
    (comp (ref "U19")
      (value "OPA454AIDDA")
      (footprint "DDA0008C_L")
      (fields (field (name "MANUFACTURER") "Texas Instruments"))
      (libsource (lib "Altium Content Vault") (part "TI-OPA454-DDA8"))
    )
    (comp (ref "U20")
      (value "OPA454AIDDA")
      (footprint "DDA0008C_L")
      (fields (field (name "MANUFACTURER") "Texas Instruments"))
      (libsource (lib "Altium Content Vault") (part "TI-OPA454-DDA8"))
    )
  )
  (nets
    (net (code "1") (name "+50V") (class "Default")
      (node (ref "U1") (pin "7") (pinfunction "V+_7") (pintype "power_in"))
      (node (ref "U10") (pin "7") (pinfunction "V+_7") (pintype "power_in"))
      (node (ref "U11") (pin "7") (pinfunction "V+_7") (pintype "power_in"))
      (node (ref "U12") (pin "7") (pinfunction "V+_7") (pintype "power_in"))
      (node (ref "U13") (pin "7") (pinfunction "V+_7") (pintype "power_in"))
      (node (ref "U14") (pin "7") (pinfunction "V+_7") (pintype "power_in"))
      (node (ref "U15") (pin "7") (pinfunction "V+_7") (pintype "power_in"))
      (node (ref "U16") (pin "7") (pinfunction "V+_7") (pintype "power_in"))
      (node (ref "U17") (pin "7") (pinfunction "V+_7") (pintype "power_in"))
      (node (ref "U18") (pin "7") (pinfunction "V+_7") (pintype "power_in"))
      (node (ref "U19") (pin "7") (pinfunction "V+_7") (pintype "power_in"))
      (node (ref "U2") (pin "7") (pinfunction "V+_7") (pintype "power_in"))
      (node (ref "U20") (pin "7") (pinfunction "V+_7") (pintype "power_in"))
      (node (ref "U3") (pin "7") (pinfunction "V+_7") (pintype "power_in"))
      (node (ref "U4") (pin "7") (pinfunction "V+_7") (pintype "power_in"))
      (node (ref "U5") (pin "7") (pinfunction "V+_7") (pintype "power_in"))
      (node (ref "U6") (pin "7") (pinfunction "V+_7") (pintype "power_in"))
      (node (ref "U7") (pin "7") (pinfunction "V+_7") (pintype "power_in"))
      (node (ref "U8") (pin "7") (pinfunction "V+_7") (pintype "power_in"))
      (node (ref "U9") (pin "7") (pinfunction "V+_7") (pintype "power_in"))
    )
    (net (code "2") (name "-50V") (class "Default")
      (node (ref "U1") (pin "4") (pinfunction "V-_4") (pintype "power_in"))
      (node (ref "U10") (pin "4") (pinfunction "V-_4") (pintype "power_in"))
      (node (ref "U11") (pin "4") (pinfunction "V-_4") (pintype "power_in"))
      (node (ref "U12") (pin "4") (pinfunction "V-_4") (pintype "power_in"))
      (node (ref "U13") (pin "4") (pinfunction "V-_4") (pintype "power_in"))
      (node (ref "U14") (pin "4") (pinfunction "V-_4") (pintype "power_in"))
      (node (ref "U15") (pin "4") (pinfunction "V-_4") (pintype "power_in"))
      (node (ref "U16") (pin "4") (pinfunction "V-_4") (pintype "power_in"))
      (node (ref "U17") (pin "4") (pinfunction "V-_4") (pintype "power_in"))
      (node (ref "U18") (pin "4") (pinfunction "V-_4") (pintype "power_in"))
      (node (ref "U19") (pin "4") (pinfunction "V-_4") (pintype "power_in"))
      (node (ref "U2") (pin "4") (pinfunction "V-_4") (pintype "power_in"))
      (node (ref "U20") (pin "4") (pinfunction "V-_4") (pintype "power_in"))
      (node (ref "U3") (pin "4") (pinfunction "V-_4") (pintype "power_in"))
      (node (ref "U4") (pin "4") (pinfunction "V-_4") (pintype "power_in"))
      (node (ref "U5") (pin "4") (pinfunction "V-_4") (pintype "power_in"))
      (node (ref "U6") (pin "4") (pinfunction "V-_4") (pintype "power_in"))
      (node (ref "U7") (pin "4") (pinfunction "V-_4") (pintype "power_in"))
      (node (ref "U8") (pin "4") (pinfunction "V-_4") (pintype "power_in"))
      (node (ref "U9") (pin "4") (pinfunction "V-_4") (pintype "power_in"))
    )
    (net (code "3") (name "GND") (class "Default")
      (node (ref "C1") (pin "2") (pinfunction "2_2") (pintype "passive"))
      (node (ref "C10") (pin "2") (pinfunction "2_2") (pintype "passive"))
      (node (ref "C11") (pin "1") (pinfunction "1_1") (pintype "passive"))
      (node (ref "C12") (pin "1") (pinfunction "1_1") (pintype "passive"))
      (node (ref "C13") (pin "1") (pinfunction "1_1") (pintype "passive"))
      (node (ref "C14") (pin "1") (pinfunction "1_1") (pintype "passive"))
      (node (ref "C15") (pin "1") (pinfunction "1_1") (pintype "passive"))
      (node (ref "C16") (pin "1") (pinfunction "1_1") (pintype "passive"))
      (node (ref "C17") (pin "1") (pinfunction "1_1") (pintype "passive"))
      (node (ref "C18") (pin "1") (pinfunction "1_1") (pintype "passive"))
      (node (ref "C19") (pin "1") (pinfunction "1_1") (pintype "passive"))
      (node (ref "C2") (pin "2") (pinfunction "2_2") (pintype "passive"))
      (node (ref "C20") (pin "1") (pinfunction "1_1") (pintype "passive"))
      (node (ref "C3") (pin "2") (pinfunction "2_2") (pintype "passive"))
      (node (ref "C4") (pin "2") (pinfunction "2_2") (pintype "passive"))
      (node (ref "C5") (pin "2") (pinfunction "2_2") (pintype "passive"))
      (node (ref "C6") (pin "2") (pinfunction "2_2") (pintype "passive"))
      (node (ref "C7") (pin "2") (pinfunction "2_2") (pintype "passive"))
      (node (ref "C8") (pin "2") (pinfunction "2_2") (pintype "passive"))
      (node (ref "C9") (pin "2") (pinfunction "2_2") (pintype "passive"))
      (node (ref "JIN") (pin "17") (pinfunction "GND1_17") (pintype "passive"))
      (node (ref "JIN") (pin "18") (pinfunction "GND2_18") (pintype "passive"))
      (node (ref "JOUT") (pin "M1") (pinfunction "M1_M1") (pintype "passive"))
      (node (ref "JOUT") (pin "M2") (pinfunction "M2_M2") (pintype "passive"))
      (node (ref "JRF1") (pin "2") (pinfunction "2_2") (pintype "passive"))
      (node (ref "JRF1") (pin "3") (pinfunction "3_3") (pintype "passive"))
      (node (ref "JRF1") (pin "4") (pinfunction "4_4") (pintype "passive"))
      (node (ref "JRF1") (pin "5") (pinfunction "5_5") (pintype "passive"))
      (node (ref "JRF2") (pin "2") (pinfunction "2_2") (pintype "passive"))
      (node (ref "JRF2") (pin "3") (pinfunction "3_3") (pintype "passive"))
      (node (ref "JRF2") (pin "4") (pinfunction "4_4") (pintype "passive"))
      (node (ref "JRF2") (pin "5") (pinfunction "5_5") (pintype "passive"))
      (node (ref "JRF3") (pin "2") (pinfunction "2_2") (pintype "passive"))
      (node (ref "JRF3") (pin "3") (pinfunction "3_3") (pintype "passive"))
      (node (ref "JRF3") (pin "4") (pinfunction "4_4") (pintype "passive"))
      (node (ref "JRF3") (pin "5") (pinfunction "5_5") (pintype "passive"))
      (node (ref "JRF4") (pin "2") (pinfunction "2_2") (pintype "passive"))
      (node (ref "JRF4") (pin "3") (pinfunction "3_3") (pintype "passive"))
      (node (ref "JRF4") (pin "4") (pinfunction "4_4") (pintype "passive"))
      (node (ref "JRF4") (pin "5") (pinfunction "5_5") (pintype "passive"))
      (node (ref "JRF5") (pin "2") (pinfunction "2_2") (pintype "passive"))
      (node (ref "JRF5") (pin "3") (pinfunction "3_3") (pintype "passive"))
      (node (ref "JRF5") (pin "4") (pinfunction "4_4") (pintype "passive"))
      (node (ref "JRF5") (pin "5") (pinfunction "5_5") (pintype "passive"))
      (node (ref "JRF6") (pin "2") (pinfunction "2_2") (pintype "passive"))
      (node (ref "JRF6") (pin "3") (pinfunction "3_3") (pintype "passive"))
      (node (ref "JRF6") (pin "4") (pinfunction "4_4") (pintype "passive"))
      (node (ref "JRF6") (pin "5") (pinfunction "5_5") (pintype "passive"))
      (node (ref "Rf8") (pin "2") (pinfunction "2_2") (pintype "passive"))
      (node (ref "Rg1") (pin "2") (pinfunction "2_2") (pintype "passive"))
      (node (ref "Rg11") (pin "2") (pinfunction "2_2") (pintype "passive"))
      (node (ref "Rg12") (pin "2") (pinfunction "2_2") (pintype "passive"))
      (node (ref "Rg13") (pin "2") (pinfunction "2_2") (pintype "passive"))
      (node (ref "Rg14") (pin "2") (pinfunction "2_2") (pintype "passive"))
      (node (ref "Rg15") (pin "2") (pinfunction "2_2") (pintype "passive"))
      (node (ref "Rg16") (pin "2") (pinfunction "2_2") (pintype "passive"))
      (node (ref "Rg17") (pin "2") (pinfunction "2_2") (pintype "passive"))
      (node (ref "Rg18") (pin "2") (pinfunction "2_2") (pintype "passive"))
      (node (ref "Rg19") (pin "2") (pinfunction "2_2") (pintype "passive"))
      (node (ref "Rg2") (pin "2") (pinfunction "2_2") (pintype "passive"))
      (node (ref "Rg20") (pin "2") (pinfunction "2_2") (pintype "passive"))
      (node (ref "Rg3") (pin "2") (pinfunction "2_2") (pintype "passive"))
      (node (ref "Rg4") (pin "2") (pinfunction "2_2") (pintype "passive"))
      (node (ref "Rg5") (pin "2") (pinfunction "2_2") (pintype "passive"))
      (node (ref "Rg6") (pin "2") (pinfunction "2_2") (pintype "passive"))
      (node (ref "Rg7") (pin "1") (pinfunction "1_1") (pintype "passive"))
      (node (ref "Rg8") (pin "2") (pinfunction "2_2") (pintype "passive"))
      (node (ref "Rg9") (pin "1") (pinfunction "1_1") (pintype "passive"))
      (node (ref "T1") (pin "1") (pinfunction "1_1") (pintype "passive"))
      (node (ref "T1") (pin "10") (pinfunction "10_10") (pintype "passive"))
      (node (ref "T1") (pin "11") (pinfunction "11_11") (pintype "passive"))
      (node (ref "T1") (pin "13") (pinfunction "13_13") (pintype "passive"))
      (node (ref "T1") (pin "14") (pinfunction "14_14") (pintype "passive"))
      (node (ref "T1") (pin "15") (pinfunction "15_15") (pintype "passive"))
      (node (ref "T1") (pin "16") (pinfunction "16_16") (pintype "passive"))
      (node (ref "T1") (pin "2") (pinfunction "2_2") (pintype "passive"))
      (node (ref "T1") (pin "4") (pinfunction "4_4") (pintype "passive"))
      (node (ref "T1") (pin "5") (pinfunction "5_5") (pintype "passive"))
      (node (ref "T1") (pin "6") (pinfunction "6_6") (pintype "passive"))
      (node (ref "T1") (pin "7") (pinfunction "7_7") (pintype "passive"))
      (node (ref "T1") (pin "8") (pinfunction "8_8") (pintype "passive"))
      (node (ref "T2") (pin "1") (pinfunction "1_1") (pintype "passive"))
      (node (ref "T2") (pin "10") (pinfunction "10_10") (pintype "passive"))
      (node (ref "T2") (pin "11") (pinfunction "11_11") (pintype "passive"))
      (node (ref "T2") (pin "13") (pinfunction "13_13") (pintype "passive"))
      (node (ref "T2") (pin "14") (pinfunction "14_14") (pintype "passive"))
      (node (ref "T2") (pin "15") (pinfunction "15_15") (pintype "passive"))
      (node (ref "T2") (pin "16") (pinfunction "16_16") (pintype "passive"))
      (node (ref "T2") (pin "2") (pinfunction "2_2") (pintype "passive"))
      (node (ref "T2") (pin "4") (pinfunction "4_4") (pintype "passive"))
      (node (ref "T2") (pin "5") (pinfunction "5_5") (pintype "passive"))
      (node (ref "T2") (pin "6") (pinfunction "6_6") (pintype "passive"))
      (node (ref "T2") (pin "7") (pinfunction "7_7") (pintype "passive"))
      (node (ref "T2") (pin "8") (pinfunction "8_8") (pintype "passive"))
      (node (ref "T3") (pin "1") (pinfunction "1_1") (pintype "passive"))
      (node (ref "T3") (pin "10") (pinfunction "10_10") (pintype "passive"))
      (node (ref "T3") (pin "11") (pinfunction "11_11") (pintype "passive"))
      (node (ref "T3") (pin "13") (pinfunction "13_13") (pintype "passive"))
      (node (ref "T3") (pin "14") (pinfunction "14_14") (pintype "passive"))
      (node (ref "T3") (pin "15") (pinfunction "15_15") (pintype "passive"))
      (node (ref "T3") (pin "16") (pinfunction "16_16") (pintype "passive"))
      (node (ref "T3") (pin "2") (pinfunction "2_2") (pintype "passive"))
      (node (ref "T3") (pin "4") (pinfunction "4_4") (pintype "passive"))
      (node (ref "T3") (pin "5") (pinfunction "5_5") (pintype "passive"))
      (node (ref "T3") (pin "6") (pinfunction "6_6") (pintype "passive"))
      (node (ref "T3") (pin "7") (pinfunction "7_7") (pintype "passive"))
      (node (ref "T3") (pin "8") (pinfunction "8_8") (pintype "passive"))
      (node (ref "T4") (pin "1") (pinfunction "1_1") (pintype "passive"))
      (node (ref "T4") (pin "10") (pinfunction "10_10") (pintype "passive"))
      (node (ref "T4") (pin "11") (pinfunction "11_11") (pintype "passive"))
      (node (ref "T4") (pin "13") (pinfunction "13_13") (pintype "passive"))
      (node (ref "T4") (pin "14") (pinfunction "14_14") (pintype "passive"))
      (node (ref "T4") (pin "15") (pinfunction "15_15") (pintype "passive"))
      (node (ref "T4") (pin "16") (pinfunction "16_16") (pintype "passive"))
      (node (ref "T4") (pin "2") (pinfunction "2_2") (pintype "passive"))
      (node (ref "T4") (pin "4") (pinfunction "4_4") (pintype "passive"))
      (node (ref "T4") (pin "5") (pinfunction "5_5") (pintype "passive"))
      (node (ref "T4") (pin "6") (pinfunction "6_6") (pintype "passive"))
      (node (ref "T4") (pin "7") (pinfunction "7_7") (pintype "passive"))
      (node (ref "T4") (pin "8") (pinfunction "8_8") (pintype "passive"))
      (node (ref "T5") (pin "1") (pinfunction "1_1") (pintype "passive"))
      (node (ref "T5") (pin "10") (pinfunction "10_10") (pintype "passive"))
      (node (ref "T5") (pin "11") (pinfunction "11_11") (pintype "passive"))
      (node (ref "T5") (pin "13") (pinfunction "13_13") (pintype "passive"))
      (node (ref "T5") (pin "14") (pinfunction "14_14") (pintype "passive"))
      (node (ref "T5") (pin "15") (pinfunction "15_15") (pintype "passive"))
      (node (ref "T5") (pin "16") (pinfunction "16_16") (pintype "passive"))
      (node (ref "T5") (pin "2") (pinfunction "2_2") (pintype "passive"))
      (node (ref "T5") (pin "4") (pinfunction "4_4") (pintype "passive"))
      (node (ref "T5") (pin "5") (pinfunction "5_5") (pintype "passive"))
      (node (ref "T5") (pin "6") (pinfunction "6_6") (pintype "passive"))
      (node (ref "T5") (pin "7") (pinfunction "7_7") (pintype "passive"))
      (node (ref "T5") (pin "8") (pinfunction "8_8") (pintype "passive"))
      (node (ref "T6") (pin "1") (pinfunction "1_1") (pintype "passive"))
      (node (ref "T6") (pin "10") (pinfunction "10_10") (pintype "passive"))
      (node (ref "T6") (pin "11") (pinfunction "11_11") (pintype "passive"))
      (node (ref "T6") (pin "13") (pinfunction "13_13") (pintype "passive"))
      (node (ref "T6") (pin "14") (pinfunction "14_14") (pintype "passive"))
      (node (ref "T6") (pin "15") (pinfunction "15_15") (pintype "passive"))
      (node (ref "T6") (pin "16") (pinfunction "16_16") (pintype "passive"))
      (node (ref "T6") (pin "2") (pinfunction "2_2") (pintype "passive"))
      (node (ref "T6") (pin "4") (pinfunction "4_4") (pintype "passive"))
      (node (ref "T6") (pin "5") (pinfunction "5_5") (pintype "passive"))
      (node (ref "T6") (pin "6") (pinfunction "6_6") (pintype "passive"))
      (node (ref "T6") (pin "7") (pinfunction "7_7") (pintype "passive"))
      (node (ref "T6") (pin "8") (pinfunction "8_8") (pintype "passive"))
    )
    (net (code "4") (name "Net-(JIN-Z0)") (class "Default")
      (node (ref "JIN") (pin "1") (pinfunction "Z0_1") (pintype "passive"))
      (node (ref "R1") (pin "1") (pinfunction "1_1") (pintype "passive"))
    )
    (net (code "5") (name "Net-(JIN-Z1)") (class "Default")
      (node (ref "JIN") (pin "2") (pinfunction "Z1_2") (pintype "passive"))
      (node (ref "R2") (pin "1") (pinfunction "1_1") (pintype "passive"))
    )
    (net (code "6") (name "Net-(JIN-Z2)") (class "Default")
      (node (ref "JIN") (pin "3") (pinfunction "Z2_3") (pintype "passive"))
      (node (ref "R3") (pin "1") (pinfunction "1_1") (pintype "passive"))
    )
    (net (code "7") (name "Net-(JIN-Z3)") (class "Default")
      (node (ref "JIN") (pin "4") (pinfunction "Z3_4") (pintype "passive"))
      (node (ref "R4") (pin "1") (pinfunction "1_1") (pintype "passive"))
    )
    (net (code "8") (name "Net-(JIN-Z4)") (class "Default")
      (node (ref "JIN") (pin "5") (pinfunction "Z4_5") (pintype "passive"))
      (node (ref "R5") (pin "1") (pinfunction "1_1") (pintype "passive"))
    )
    (net (code "9") (name "Net-(JIN-Z5)") (class "Default")
      (node (ref "JIN") (pin "6") (pinfunction "Z5_6") (pintype "passive"))
      (node (ref "R6") (pin "1") (pinfunction "1_1") (pintype "passive"))
    )
    (net (code "10") (name "Net-(JIN-Z6)") (class "Default")
      (node (ref "JIN") (pin "7") (pinfunction "Z6_7") (pintype "passive"))
      (node (ref "R7") (pin "1") (pinfunction "1_1") (pintype "passive"))
    )
    (net (code "11") (name "Net-(JIN-Z7)") (class "Default")
      (node (ref "JIN") (pin "8") (pinfunction "Z7_8") (pintype "passive"))
      (node (ref "R8") (pin "1") (pinfunction "1_1") (pintype "passive"))
    )
    (net (code "12") (name "Net-(JIN-Z8)") (class "Default")
      (node (ref "JIN") (pin "9") (pinfunction "Z8_9") (pintype "passive"))
      (node (ref "R9") (pin "1") (pinfunction "1_1") (pintype "passive"))
    )
    (net (code "13") (name "Net-(JIN-Z9)") (class "Default")
      (node (ref "JIN") (pin "10") (pinfunction "Z9_10") (pintype "passive"))
      (node (ref "R10") (pin "1") (pinfunction "1_1") (pintype "passive"))
    )
    (net (code "14") (name "Net-(JIN-Z10)") (class "Default")
      (node (ref "JIN") (pin "11") (pinfunction "Z10_11") (pintype "passive"))
      (node (ref "R11") (pin "1") (pinfunction "1_1") (pintype "passive"))
    )
    (net (code "15") (name "Net-(JIN-Z11)") (class "Default")
      (node (ref "JIN") (pin "12") (pinfunction "Z11_12") (pintype "passive"))
      (node (ref "R12") (pin "1") (pinfunction "1_1") (pintype "passive"))
    )
    (net (code "16") (name "Net-(JIN-Z12)") (class "Default")
      (node (ref "JIN") (pin "13") (pinfunction "Z12_13") (pintype "passive"))
      (node (ref "R13") (pin "1") (pinfunction "1_1") (pintype "passive"))
    )
    (net (code "17") (name "Net-(JIN-Z13)") (class "Default")
      (node (ref "JIN") (pin "14") (pinfunction "Z13_14") (pintype "passive"))
      (node (ref "R14") (pin "1") (pinfunction "1_1") (pintype "passive"))
    )
    (net (code "18") (name "Net-(JIN-Z14)") (class "Default")
      (node (ref "JIN") (pin "15") (pinfunction "Z14_15") (pintype "passive"))
      (node (ref "R15") (pin "1") (pinfunction "1_1") (pintype "passive"))
    )
    (net (code "19") (name "Net-(JIN-Z15)") (class "Default")
      (node (ref "JIN") (pin "16") (pinfunction "Z15_16") (pintype "passive"))
      (node (ref "R16") (pin "1") (pinfunction "1_1") (pintype "passive"))
    )
    (net (code "20") (name "Net-(JIN-Z16)") (class "Default")
      (node (ref "JIN") (pin "19") (pinfunction "Z16_19") (pintype "passive"))
      (node (ref "R17") (pin "1") (pinfunction "1_1") (pintype "passive"))
    )
    (net (code "21") (name "Net-(JIN-Z17)") (class "Default")
      (node (ref "JIN") (pin "20") (pinfunction "Z17_20") (pintype "passive"))
      (node (ref "R18") (pin "1") (pinfunction "1_1") (pintype "passive"))
    )
    (net (code "22") (name "Net-(JIN-Z18)") (class "Default")
      (node (ref "JIN") (pin "21") (pinfunction "Z18_21") (pintype "passive"))
      (node (ref "R19") (pin "1") (pinfunction "1_1") (pintype "passive"))
    )
    (net (code "23") (name "Net-(JIN-Z19)") (class "Default")
      (node (ref "JIN") (pin "22") (pinfunction "Z19_22") (pintype "passive"))
      (node (ref "R20") (pin "1") (pinfunction "1_1") (pintype "passive"))
    )
    (net (code "24") (name "Net-(T1-DC)") (class "Default")
      (node (ref "Rf1") (pin "2") (pinfunction "2_2") (pintype "passive"))
      (node (ref "Rg1") (pin "1") (pinfunction "1_1") (pintype "passive"))
      (node (ref "T1") (pin "3") (pinfunction "DC_3") (pintype "input"))
      (node (ref "U1") (pin "6") (pinfunction "OUT_6") (pintype "output"))
    )
    (net (code "25") (name "Net-(T1-RF)") (class "Default")
      (node (ref "JRF1") (pin "1") (pinfunction "1_1") (pintype "passive"))
      (node (ref "T1") (pin "9") (pinfunction "RF_9") (pintype "input"))
    )
    (net (code "26") (name "Net-(T1-RF+DC)") (class "Default")
      (node (ref "JOUT") (pin "1") (pinfunction "1_1") (pintype "passive"))
      (node (ref "T1") (pin "12") (pinfunction "RF+DC_12") (pintype "output"))
    )
    (net (code "27") (name "Net-(T2-DC)") (class "Default")
      (node (ref "Rf3") (pin "2") (pinfunction "2_2") (pintype "passive"))
      (node (ref "Rg3") (pin "1") (pinfunction "1_1") (pintype "passive"))
      (node (ref "T2") (pin "3") (pinfunction "DC_3") (pintype "input"))
      (node (ref "U3") (pin "6") (pinfunction "OUT_6") (pintype "output"))
    )
    (net (code "28") (name "Net-(T2-RF)") (class "Default")
      (node (ref "JRF2") (pin "1") (pinfunction "1_1") (pintype "passive"))
      (node (ref "T2") (pin "9") (pinfunction "RF_9") (pintype "input"))
    )
    (net (code "29") (name "Net-(T2-RF+DC)") (class "Default")
      (node (ref "JOUT") (pin "3") (pinfunction "3_3") (pintype "passive"))
      (node (ref "T2") (pin "12") (pinfunction "RF+DC_12") (pintype "output"))
    )
    (net (code "30") (name "Net-(T3-DC)") (class "Default")
      (node (ref "Rg10") (pin "1") (pinfunction "1_1") (pintype "passive"))
      (node (ref "Rg9") (pin "2") (pinfunction "2_2") (pintype "passive"))
      (node (ref "T3") (pin "3") (pinfunction "DC_3") (pintype "input"))
      (node (ref "U8") (pin "6") (pinfunction "OUT_6") (pintype "output"))
    )
    (net (code "31") (name "Net-(T3-RF)") (class "Default")
      (node (ref "JRF3") (pin "1") (pinfunction "1_1") (pintype "passive"))
      (node (ref "T3") (pin "9") (pinfunction "RF_9") (pintype "input"))
    )
    (net (code "32") (name "Net-(T3-RF+DC)") (class "Default")
      (node (ref "JOUT") (pin "8") (pinfunction "8_8") (pintype "passive"))
      (node (ref "T3") (pin "12") (pinfunction "RF+DC_12") (pintype "output"))
    )
    (net (code "33") (name "Net-(T4-DC)") (class "Default")
      (node (ref "Rf10") (pin "2") (pinfunction "2_2") (pintype "passive"))
      (node (ref "Rf8") (pin "1") (pinfunction "1_1") (pintype "passive"))
      (node (ref "T4") (pin "3") (pinfunction "DC_3") (pintype "input"))
      (node (ref "U10") (pin "6") (pinfunction "OUT_6") (pintype "output"))
    )
    (net (code "34") (name "Net-(T4-RF)") (class "Default")
      (node (ref "JRF4") (pin "1") (pinfunction "1_1") (pintype "passive"))
      (node (ref "T4") (pin "9") (pinfunction "RF_9") (pintype "input"))
    )
    (net (code "35") (name "Net-(T4-RF+DC)") (class "Default")
      (node (ref "JOUT") (pin "10") (pinfunction "10_10") (pintype "passive"))
      (node (ref "T4") (pin "12") (pinfunction "RF+DC_12") (pintype "output"))
    )
    (net (code "36") (name "Net-(T5-DC)") (class "Default")
      (node (ref "Rf12") (pin "2") (pinfunction "2_2") (pintype "passive"))
      (node (ref "Rg12") (pin "1") (pinfunction "1_1") (pintype "passive"))
      (node (ref "T5") (pin "3") (pinfunction "DC_3") (pintype "input"))
      (node (ref "U12") (pin "6") (pinfunction "OUT_6") (pintype "output"))
    )
    (net (code "37") (name "Net-(T5-RF)") (class "Default")
      (node (ref "JRF5") (pin "1") (pinfunction "1_1") (pintype "passive"))
      (node (ref "T5") (pin "9") (pinfunction "RF_9") (pintype "input"))
    )
    (net (code "38") (name "Net-(T5-RF+DC)") (class "Default")
      (node (ref "JOUT") (pin "12") (pinfunction "12_12") (pintype "passive"))
      (node (ref "T5") (pin "12") (pinfunction "RF+DC_12") (pintype "output"))
    )
    (net (code "39") (name "Net-(T6-DC)") (class "Default")
      (node (ref "Rf19") (pin "2") (pinfunction "2_2") (pintype "passive"))
      (node (ref "Rg19") (pin "1") (pinfunction "1_1") (pintype "passive"))
      (node (ref "T6") (pin "3") (pinfunction "DC_3") (pintype "input"))
      (node (ref "U19") (pin "6") (pinfunction "OUT_6") (pintype "output"))
    )
    (net (code "40") (name "Net-(T6-RF)") (class "Default")
      (node (ref "JRF6") (pin "1") (pinfunction "1_1") (pintype "passive"))
      (node (ref "T6") (pin "9") (pinfunction "RF_9") (pintype "input"))
    )
    (net (code "41") (name "Net-(T6-RF+DC)") (class "Default")
      (node (ref "JOUT") (pin "19") (pinfunction "19_19") (pintype "passive"))
      (node (ref "T6") (pin "12") (pinfunction "RF+DC_12") (pintype "output"))
    )
    (net (code "42") (name "Net-(U1-IN+)") (class "Default")
      (node (ref "C1") (pin "1") (pinfunction "1_1") (pintype "passive"))
      (node (ref "R1") (pin "2") (pinfunction "2_2") (pintype "passive"))
      (node (ref "U1") (pin "3") (pinfunction "IN+_3") (pintype "input"))
    )
    (net (code "43") (name "Net-(U1-IN-)") (class "Default")
      (node (ref "Rf1") (pin "1") (pinfunction "1_1") (pintype "passive"))
      (node (ref "U1") (pin "2") (pinfunction "IN-_2") (pintype "input"))
    )
    (net (code "44") (name "Net-(U2-IN+)") (class "Default")
      (node (ref "C2") (pin "1") (pinfunction "1_1") (pintype "passive"))
      (node (ref "R2") (pin "2") (pinfunction "2_2") (pintype "passive"))
      (node (ref "U2") (pin "3") (pinfunction "IN+_3") (pintype "input"))
    )
    (net (code "45") (name "Net-(U2-IN-)") (class "Default")
      (node (ref "Rf2") (pin "1") (pinfunction "1_1") (pintype "passive"))
      (node (ref "U2") (pin "2") (pinfunction "IN-_2") (pintype "input"))
    )
    (net (code "46") (name "Net-(U2-OUT)") (class "Default")
      (node (ref "JOUT") (pin "2") (pinfunction "2_2") (pintype "passive"))
      (node (ref "Rf2") (pin "2") (pinfunction "2_2") (pintype "passive"))
      (node (ref "Rg2") (pin "1") (pinfunction "1_1") (pintype "passive"))
      (node (ref "U2") (pin "6") (pinfunction "OUT_6") (pintype "output"))
    )
    (net (code "47") (name "Net-(U3-IN+)") (class "Default")
      (node (ref "C3") (pin "1") (pinfunction "1_1") (pintype "passive"))
      (node (ref "R3") (pin "2") (pinfunction "2_2") (pintype "passive"))
      (node (ref "U3") (pin "3") (pinfunction "IN+_3") (pintype "input"))
    )
    (net (code "48") (name "Net-(U3-IN-)") (class "Default")
      (node (ref "Rf3") (pin "1") (pinfunction "1_1") (pintype "passive"))
      (node (ref "U3") (pin "2") (pinfunction "IN-_2") (pintype "input"))
    )
    (net (code "49") (name "Net-(U4-IN+)") (class "Default")
      (node (ref "C4") (pin "1") (pinfunction "1_1") (pintype "passive"))
      (node (ref "R4") (pin "2") (pinfunction "2_2") (pintype "passive"))
      (node (ref "U4") (pin "3") (pinfunction "IN+_3") (pintype "input"))
    )
    (net (code "50") (name "Net-(U4-IN-)") (class "Default")
      (node (ref "Rf4") (pin "1") (pinfunction "1_1") (pintype "passive"))
      (node (ref "U4") (pin "2") (pinfunction "IN-_2") (pintype "input"))
    )
    (net (code "51") (name "Net-(U4-OUT)") (class "Default")
      (node (ref "JOUT") (pin "4") (pinfunction "4_4") (pintype "passive"))
      (node (ref "Rf4") (pin "2") (pinfunction "2_2") (pintype "passive"))
      (node (ref "Rg4") (pin "1") (pinfunction "1_1") (pintype "passive"))
      (node (ref "U4") (pin "6") (pinfunction "OUT_6") (pintype "output"))
    )
    (net (code "52") (name "Net-(U5-IN+)") (class "Default")
      (node (ref "C5") (pin "1") (pinfunction "1_1") (pintype "passive"))
      (node (ref "R5") (pin "2") (pinfunction "2_2") (pintype "passive"))
      (node (ref "U5") (pin "3") (pinfunction "IN+_3") (pintype "input"))
    )
    (net (code "53") (name "Net-(U5-IN-)") (class "Default")
      (node (ref "Rf5") (pin "1") (pinfunction "1_1") (pintype "passive"))
      (node (ref "U5") (pin "2") (pinfunction "IN-_2") (pintype "input"))
    )
    (net (code "54") (name "Net-(U5-OUT)") (class "Default")
      (node (ref "JOUT") (pin "5") (pinfunction "5_5") (pintype "passive"))
      (node (ref "Rf5") (pin "2") (pinfunction "2_2") (pintype "passive"))
      (node (ref "Rg5") (pin "1") (pinfunction "1_1") (pintype "passive"))
      (node (ref "U5") (pin "6") (pinfunction "OUT_6") (pintype "output"))
    )
    (net (code "55") (name "Net-(U6-IN+)") (class "Default")
      (node (ref "C6") (pin "1") (pinfunction "1_1") (pintype "passive"))
      (node (ref "R6") (pin "2") (pinfunction "2_2") (pintype "passive"))
      (node (ref "U6") (pin "3") (pinfunction "IN+_3") (pintype "input"))
    )
    (net (code "56") (name "Net-(U6-IN-)") (class "Default")
      (node (ref "Rf6") (pin "1") (pinfunction "1_1") (pintype "passive"))
      (node (ref "U6") (pin "2") (pinfunction "IN-_2") (pintype "input"))
    )
    (net (code "57") (name "Net-(U6-OUT)") (class "Default")
      (node (ref "JOUT") (pin "6") (pinfunction "6_6") (pintype "passive"))
      (node (ref "Rf6") (pin "2") (pinfunction "2_2") (pintype "passive"))
      (node (ref "Rg6") (pin "1") (pinfunction "1_1") (pintype "passive"))
      (node (ref "U6") (pin "6") (pinfunction "OUT_6") (pintype "output"))
    )
    (net (code "58") (name "Net-(U7-IN+)") (class "Default")
      (node (ref "C7") (pin "1") (pinfunction "1_1") (pintype "passive"))
      (node (ref "R7") (pin "2") (pinfunction "2_2") (pintype "passive"))
      (node (ref "U7") (pin "3") (pinfunction "IN+_3") (pintype "input"))
    )
    (net (code "59") (name "Net-(U7-IN-)") (class "Default")
      (node (ref "Rf7") (pin "2") (pinfunction "2_2") (pintype "passive"))
      (node (ref "U7") (pin "2") (pinfunction "IN-_2") (pintype "input"))
    )
    (net (code "60") (name "Net-(U7-OUT)") (class "Default")
      (node (ref "JOUT") (pin "7") (pinfunction "7_7") (pintype "passive"))
      (node (ref "Rf7") (pin "1") (pinfunction "1_1") (pintype "passive"))
      (node (ref "Rg7") (pin "2") (pinfunction "2_2") (pintype "passive"))
      (node (ref "U7") (pin "6") (pinfunction "OUT_6") (pintype "output"))
    )
    (net (code "61") (name "Net-(U8-IN+)") (class "Default")
      (node (ref "C8") (pin "1") (pinfunction "1_1") (pintype "passive"))
      (node (ref "R8") (pin "2") (pinfunction "2_2") (pintype "passive"))
      (node (ref "U8") (pin "3") (pinfunction "IN+_3") (pintype "input"))
    )
    (net (code "62") (name "Net-(U8-IN-)") (class "Default")
      (node (ref "Rg10") (pin "2") (pinfunction "2_2") (pintype "passive"))
      (node (ref "U8") (pin "2") (pinfunction "IN-_2") (pintype "input"))
    )
    (net (code "63") (name "Net-(U9-IN+)") (class "Default")
      (node (ref "C9") (pin "1") (pinfunction "1_1") (pintype "passive"))
      (node (ref "R9") (pin "2") (pinfunction "2_2") (pintype "passive"))
      (node (ref "U9") (pin "3") (pinfunction "IN+_3") (pintype "input"))
    )
    (net (code "64") (name "Net-(U9-IN-)") (class "Default")
      (node (ref "Rf9") (pin "1") (pinfunction "1_1") (pintype "passive"))
      (node (ref "U9") (pin "2") (pinfunction "IN-_2") (pintype "input"))
    )
    (net (code "65") (name "Net-(U9-OUT)") (class "Default")
      (node (ref "JOUT") (pin "9") (pinfunction "9_9") (pintype "passive"))
      (node (ref "Rf9") (pin "2") (pinfunction "2_2") (pintype "passive"))
      (node (ref "Rg8") (pin "1") (pinfunction "1_1") (pintype "passive"))
      (node (ref "U9") (pin "6") (pinfunction "OUT_6") (pintype "output"))
    )
    (net (code "66") (name "Net-(U10-IN+)") (class "Default")
      (node (ref "C10") (pin "1") (pinfunction "1_1") (pintype "passive"))
      (node (ref "R10") (pin "2") (pinfunction "2_2") (pintype "passive"))
      (node (ref "U10") (pin "3") (pinfunction "IN+_3") (pintype "input"))
    )
    (net (code "67") (name "Net-(U10-IN-)") (class "Default")
      (node (ref "Rf10") (pin "1") (pinfunction "1_1") (pintype "passive"))
      (node (ref "U10") (pin "2") (pinfunction "IN-_2") (pintype "input"))
    )
    (net (code "68") (name "Net-(U11-IN+)") (class "Default")
      (node (ref "C11") (pin "2") (pinfunction "2_2") (pintype "passive"))
      (node (ref "R11") (pin "2") (pinfunction "2_2") (pintype "passive"))
      (node (ref "U11") (pin "3") (pinfunction "IN+_3") (pintype "input"))
    )
    (net (code "69") (name "Net-(U11-IN-)") (class "Default")
      (node (ref "Rf11") (pin "1") (pinfunction "1_1") (pintype "passive"))
      (node (ref "U11") (pin "2") (pinfunction "IN-_2") (pintype "input"))
    )
    (net (code "70") (name "Net-(U11-OUT)") (class "Default")
      (node (ref "JOUT") (pin "11") (pinfunction "11_11") (pintype "passive"))
      (node (ref "Rf11") (pin "2") (pinfunction "2_2") (pintype "passive"))
      (node (ref "Rg11") (pin "1") (pinfunction "1_1") (pintype "passive"))
      (node (ref "U11") (pin "6") (pinfunction "OUT_6") (pintype "output"))
    )
    (net (code "71") (name "Net-(U12-IN+)") (class "Default")
      (node (ref "C12") (pin "2") (pinfunction "2_2") (pintype "passive"))
      (node (ref "R12") (pin "2") (pinfunction "2_2") (pintype "passive"))
      (node (ref "U12") (pin "3") (pinfunction "IN+_3") (pintype "input"))
    )
    (net (code "72") (name "Net-(U12-IN-)") (class "Default")
      (node (ref "Rf12") (pin "1") (pinfunction "1_1") (pintype "passive"))
      (node (ref "U12") (pin "2") (pinfunction "IN-_2") (pintype "input"))
    )
    (net (code "73") (name "Net-(U13-IN+)") (class "Default")
      (node (ref "C13") (pin "2") (pinfunction "2_2") (pintype "passive"))
      (node (ref "R13") (pin "2") (pinfunction "2_2") (pintype "passive"))
      (node (ref "U13") (pin "3") (pinfunction "IN+_3") (pintype "input"))
    )
    (net (code "74") (name "Net-(U13-IN-)") (class "Default")
      (node (ref "Rf13") (pin "1") (pinfunction "1_1") (pintype "passive"))
      (node (ref "U13") (pin "2") (pinfunction "IN-_2") (pintype "input"))
    )
    (net (code "75") (name "Net-(U13-OUT)") (class "Default")
      (node (ref "JOUT") (pin "13") (pinfunction "13_13") (pintype "passive"))
      (node (ref "Rf13") (pin "2") (pinfunction "2_2") (pintype "passive"))
      (node (ref "Rg13") (pin "1") (pinfunction "1_1") (pintype "passive"))
      (node (ref "U13") (pin "6") (pinfunction "OUT_6") (pintype "output"))
    )
    (net (code "76") (name "Net-(U14-IN+)") (class "Default")
      (node (ref "C14") (pin "2") (pinfunction "2_2") (pintype "passive"))
      (node (ref "R14") (pin "2") (pinfunction "2_2") (pintype "passive"))
      (node (ref "U14") (pin "3") (pinfunction "IN+_3") (pintype "input"))
    )
    (net (code "77") (name "Net-(U14-IN-)") (class "Default")
      (node (ref "Rf14") (pin "1") (pinfunction "1_1") (pintype "passive"))
      (node (ref "U14") (pin "2") (pinfunction "IN-_2") (pintype "input"))
    )
    (net (code "78") (name "Net-(U14-OUT)") (class "Default")
      (node (ref "JOUT") (pin "14") (pinfunction "14_14") (pintype "passive"))
      (node (ref "Rf14") (pin "2") (pinfunction "2_2") (pintype "passive"))
      (node (ref "Rg14") (pin "1") (pinfunction "1_1") (pintype "passive"))
      (node (ref "U14") (pin "6") (pinfunction "OUT_6") (pintype "output"))
    )
    (net (code "79") (name "Net-(U15-IN+)") (class "Default")
      (node (ref "C15") (pin "2") (pinfunction "2_2") (pintype "passive"))
      (node (ref "R15") (pin "2") (pinfunction "2_2") (pintype "passive"))
      (node (ref "U15") (pin "3") (pinfunction "IN+_3") (pintype "input"))
    )
    (net (code "80") (name "Net-(U15-IN-)") (class "Default")
      (node (ref "Rf15") (pin "1") (pinfunction "1_1") (pintype "passive"))
      (node (ref "U15") (pin "2") (pinfunction "IN-_2") (pintype "input"))
    )
    (net (code "81") (name "Net-(U15-OUT)") (class "Default")
      (node (ref "JOUT") (pin "15") (pinfunction "15_15") (pintype "passive"))
      (node (ref "Rf15") (pin "2") (pinfunction "2_2") (pintype "passive"))
      (node (ref "Rg15") (pin "1") (pinfunction "1_1") (pintype "passive"))
      (node (ref "U15") (pin "6") (pinfunction "OUT_6") (pintype "output"))
    )
    (net (code "82") (name "Net-(U16-IN+)") (class "Default")
      (node (ref "C16") (pin "2") (pinfunction "2_2") (pintype "passive"))
      (node (ref "R16") (pin "2") (pinfunction "2_2") (pintype "passive"))
      (node (ref "U16") (pin "3") (pinfunction "IN+_3") (pintype "input"))
    )
    (net (code "83") (name "Net-(U16-IN-)") (class "Default")
      (node (ref "Rf16") (pin "1") (pinfunction "1_1") (pintype "passive"))
      (node (ref "U16") (pin "2") (pinfunction "IN-_2") (pintype "input"))
    )
    (net (code "84") (name "Net-(U16-OUT)") (class "Default")
      (node (ref "JOUT") (pin "16") (pinfunction "16_16") (pintype "passive"))
      (node (ref "Rf16") (pin "2") (pinfunction "2_2") (pintype "passive"))
      (node (ref "Rg16") (pin "1") (pinfunction "1_1") (pintype "passive"))
      (node (ref "U16") (pin "6") (pinfunction "OUT_6") (pintype "output"))
    )
    (net (code "85") (name "Net-(U17-IN+)") (class "Default")
      (node (ref "C17") (pin "2") (pinfunction "2_2") (pintype "passive"))
      (node (ref "R17") (pin "2") (pinfunction "2_2") (pintype "passive"))
      (node (ref "U17") (pin "3") (pinfunction "IN+_3") (pintype "input"))
    )
    (net (code "86") (name "Net-(U17-IN-)") (class "Default")
      (node (ref "Rf17") (pin "1") (pinfunction "1_1") (pintype "passive"))
      (node (ref "U17") (pin "2") (pinfunction "IN-_2") (pintype "input"))
    )
    (net (code "87") (name "Net-(U17-OUT)") (class "Default")
      (node (ref "JOUT") (pin "17") (pinfunction "17_17") (pintype "passive"))
      (node (ref "Rf17") (pin "2") (pinfunction "2_2") (pintype "passive"))
      (node (ref "Rg17") (pin "1") (pinfunction "1_1") (pintype "passive"))
      (node (ref "U17") (pin "6") (pinfunction "OUT_6") (pintype "output"))
    )
    (net (code "88") (name "Net-(U18-IN+)") (class "Default")
      (node (ref "C18") (pin "2") (pinfunction "2_2") (pintype "passive"))
      (node (ref "R18") (pin "2") (pinfunction "2_2") (pintype "passive"))
      (node (ref "U18") (pin "3") (pinfunction "IN+_3") (pintype "input"))
    )
    (net (code "89") (name "Net-(U18-IN-)") (class "Default")
      (node (ref "Rf18") (pin "1") (pinfunction "1_1") (pintype "passive"))
      (node (ref "U18") (pin "2") (pinfunction "IN-_2") (pintype "input"))
    )
    (net (code "90") (name "Net-(U18-OUT)") (class "Default")
      (node (ref "JOUT") (pin "18") (pinfunction "18_18") (pintype "passive"))
      (node (ref "Rf18") (pin "2") (pinfunction "2_2") (pintype "passive"))
      (node (ref "Rg18") (pin "1") (pinfunction "1_1") (pintype "passive"))
      (node (ref "U18") (pin "6") (pinfunction "OUT_6") (pintype "output"))
    )
    (net (code "91") (name "Net-(U19-IN+)") (class "Default")
      (node (ref "C19") (pin "2") (pinfunction "2_2") (pintype "passive"))
      (node (ref "R19") (pin "2") (pinfunction "2_2") (pintype "passive"))
      (node (ref "U19") (pin "3") (pinfunction "IN+_3") (pintype "input"))
    )
    (net (code "92") (name "Net-(U19-IN-)") (class "Default")
      (node (ref "Rf19") (pin "1") (pinfunction "1_1") (pintype "passive"))
      (node (ref "U19") (pin "2") (pinfunction "IN-_2") (pintype "input"))
    )
    (net (code "93") (name "Net-(U20-IN+)") (class "Default")
      (node (ref "C20") (pin "2") (pinfunction "2_2") (pintype "passive"))
      (node (ref "R20") (pin "2") (pinfunction "2_2") (pintype "passive"))
      (node (ref "U20") (pin "3") (pinfunction "IN+_3") (pintype "input"))
    )
    (net (code "94") (name "Net-(U20-IN-)") (class "Default")
      (node (ref "Rf20") (pin "1") (pinfunction "1_1") (pintype "passive"))
      (node (ref "U20") (pin "2") (pinfunction "IN-_2") (pintype "input"))
    )
    (net (code "95") (name "Net-(U20-OUT)") (class "Default")
      (node (ref "JOUT") (pin "20") (pinfunction "20_20") (pintype "passive"))
      (node (ref "Rf20") (pin "2") (pinfunction "2_2") (pintype "passive"))
      (node (ref "Rg20") (pin "1") (pinfunction "1_1") (pintype "passive"))
      (node (ref "U20") (pin "6") (pinfunction "OUT_6") (pintype "output"))
    )
    (net (code "96") (name "unconnected-(JIN-Pad35)") (class "Default")
      (node (ref "JIN") (pin "35") (pinfunction "35_35") (pintype "passive"))
    )
    (net (code "97") (name "unconnected-(JIN-Pad36)") (class "Default")
      (node (ref "JIN") (pin "36") (pinfunction "36_36") (pintype "passive"))
    )
    (net (code "98") (name "unconnected-(JIN-Pad37)") (class "Default")
      (node (ref "JIN") (pin "37") (pinfunction "37_37") (pintype "passive"))
    )
    (net (code "99") (name "unconnected-(JIN-Pad38)") (class "Default")
      (node (ref "JIN") (pin "38") (pinfunction "38_38") (pintype "passive"))
    )
    (net (code "100") (name "unconnected-(JIN-Pad39)") (class "Default")
      (node (ref "JIN") (pin "39") (pinfunction "39_39") (pintype "passive"))
    )
    (net (code "101") (name "unconnected-(JIN-Pad40)") (class "Default")
      (node (ref "JIN") (pin "40") (pinfunction "40_40") (pintype "passive"))
    )
    (net (code "102") (name "unconnected-(JIN-Pad41)") (class "Default")
      (node (ref "JIN") (pin "41") (pinfunction "41_41") (pintype "passive"))
    )
    (net (code "103") (name "unconnected-(JIN-Pad42)") (class "Default")
      (node (ref "JIN") (pin "42") (pinfunction "42_42") (pintype "passive"))
    )
    (net (code "104") (name "unconnected-(JIN-Pad43)") (class "Default")
      (node (ref "JIN") (pin "43") (pinfunction "43_43") (pintype "passive"))
    )
    (net (code "105") (name "unconnected-(JIN-Pad44)") (class "Default")
      (node (ref "JIN") (pin "44") (pinfunction "44_44") (pintype "passive"))
    )
    (net (code "106") (name "unconnected-(JIN-Pad45)") (class "Default")
      (node (ref "JIN") (pin "45") (pinfunction "45_45") (pintype "passive"))
    )
    (net (code "107") (name "unconnected-(JIN-Pad46)") (class "Default")
      (node (ref "JIN") (pin "46") (pinfunction "46_46") (pintype "passive"))
    )
    (net (code "108") (name "unconnected-(JIN-Pad47)") (class "Default")
      (node (ref "JIN") (pin "47") (pinfunction "47_47") (pintype "passive"))
    )
    (net (code "109") (name "unconnected-(JIN-Pad48)") (class "Default")
      (node (ref "JIN") (pin "48") (pinfunction "48_48") (pintype "passive"))
    )
    (net (code "110") (name "unconnected-(JIN-Pad49)") (class "Default")
      (node (ref "JIN") (pin "49") (pinfunction "49_49") (pintype "passive"))
    )
    (net (code "111") (name "unconnected-(JIN-Pad50)") (class "Default")
      (node (ref "JIN") (pin "50") (pinfunction "50_50") (pintype "passive"))
    )
    (net (code "112") (name "unconnected-(JIN-Pad51)") (class "Default")
      (node (ref "JIN") (pin "51") (pinfunction "51_51") (pintype "passive"))
    )
    (net (code "113") (name "unconnected-(JIN-Pad52)") (class "Default")
      (node (ref "JIN") (pin "52") (pinfunction "52_52") (pintype "passive"))
    )
    (net (code "114") (name "unconnected-(JIN-Pad53)") (class "Default")
      (node (ref "JIN") (pin "53") (pinfunction "53_53") (pintype "passive"))
    )
    (net (code "115") (name "unconnected-(JIN-Pad54)") (class "Default")
      (node (ref "JIN") (pin "54") (pinfunction "54_54") (pintype "passive"))
    )
    (net (code "116") (name "unconnected-(JIN-Pad55)") (class "Default")
      (node (ref "JIN") (pin "55") (pinfunction "55_55") (pintype "passive"))
    )
    (net (code "117") (name "unconnected-(JIN-Pad56)") (class "Default")
      (node (ref "JIN") (pin "56") (pinfunction "56_56") (pintype "passive"))
    )
    (net (code "118") (name "unconnected-(JIN-Pad57)") (class "Default")
      (node (ref "JIN") (pin "57") (pinfunction "57_57") (pintype "passive"))
    )
    (net (code "119") (name "unconnected-(JIN-Pad58)") (class "Default")
      (node (ref "JIN") (pin "58") (pinfunction "58_58") (pintype "passive"))
    )
    (net (code "120") (name "unconnected-(JIN-Pad59)") (class "Default")
      (node (ref "JIN") (pin "59") (pinfunction "59_59") (pintype "passive"))
    )
    (net (code "121") (name "unconnected-(JIN-Pad60)") (class "Default")
      (node (ref "JIN") (pin "60") (pinfunction "60_60") (pintype "passive"))
    )
    (net (code "122") (name "unconnected-(JIN-Pad61)") (class "Default")
      (node (ref "JIN") (pin "61") (pinfunction "61_61") (pintype "passive"))
    )
    (net (code "123") (name "unconnected-(JIN-Pad62)") (class "Default")
      (node (ref "JIN") (pin "62") (pinfunction "62_62") (pintype "passive"))
    )
    (net (code "124") (name "unconnected-(JIN-Pad63)") (class "Default")
      (node (ref "JIN") (pin "63") (pinfunction "63_63") (pintype "passive"))
    )
    (net (code "125") (name "unconnected-(JIN-Pad64)") (class "Default")
      (node (ref "JIN") (pin "64") (pinfunction "64_64") (pintype "passive"))
    )
    (net (code "126") (name "unconnected-(JIN-Pad65)") (class "Default")
      (node (ref "JIN") (pin "65") (pinfunction "65_65") (pintype "passive"))
    )
    (net (code "127") (name "unconnected-(JIN-Pad66)") (class "Default")
      (node (ref "JIN") (pin "66") (pinfunction "66_66") (pintype "passive"))
    )
    (net (code "128") (name "unconnected-(JIN-Pad67)") (class "Default")
      (node (ref "JIN") (pin "67") (pinfunction "67_67") (pintype "passive"))
    )
    (net (code "129") (name "unconnected-(JIN-Pad68)") (class "Default")
      (node (ref "JIN") (pin "68") (pinfunction "68_68") (pintype "passive"))
    )
    (net (code "130") (name "unconnected-(JIN-PadM1)") (class "Default")
      (node (ref "JIN") (pin "M1") (pinfunction "M1_M1") (pintype "passive"))
    )
    (net (code "131") (name "unconnected-(JIN-PadM2)") (class "Default")
      (node (ref "JIN") (pin "M2") (pinfunction "M2_M2") (pintype "passive"))
    )
    (net (code "132") (name "unconnected-(JIN-Z20-Pad23)") (class "Default")
      (node (ref "JIN") (pin "23") (pinfunction "Z20_23") (pintype "passive"))
    )
    (net (code "133") (name "unconnected-(JIN-Z21-Pad24)") (class "Default")
      (node (ref "JIN") (pin "24") (pinfunction "Z21_24") (pintype "passive"))
    )
    (net (code "134") (name "unconnected-(JIN-Z22-Pad25)") (class "Default")
      (node (ref "JIN") (pin "25") (pinfunction "Z22_25") (pintype "passive"))
    )
    (net (code "135") (name "unconnected-(JIN-Z23-Pad26)") (class "Default")
      (node (ref "JIN") (pin "26") (pinfunction "Z23_26") (pintype "passive"))
    )
    (net (code "136") (name "unconnected-(JIN-Z24-Pad27)") (class "Default")
      (node (ref "JIN") (pin "27") (pinfunction "Z24_27") (pintype "passive"))
    )
    (net (code "137") (name "unconnected-(JIN-Z25-Pad28)") (class "Default")
      (node (ref "JIN") (pin "28") (pinfunction "Z25_28") (pintype "passive"))
    )
    (net (code "138") (name "unconnected-(JIN-Z26-Pad29)") (class "Default")
      (node (ref "JIN") (pin "29") (pinfunction "Z26_29") (pintype "passive"))
    )
    (net (code "139") (name "unconnected-(JIN-Z27-Pad30)") (class "Default")
      (node (ref "JIN") (pin "30") (pinfunction "Z27_30") (pintype "passive"))
    )
    (net (code "140") (name "unconnected-(JIN-Z28-Pad31)") (class "Default")
      (node (ref "JIN") (pin "31") (pinfunction "Z28_31") (pintype "passive"))
    )
    (net (code "141") (name "unconnected-(JIN-Z29-Pad32)") (class "Default")
      (node (ref "JIN") (pin "32") (pinfunction "Z29_32") (pintype "passive"))
    )
    (net (code "142") (name "unconnected-(JIN-Z30-Pad33)") (class "Default")
      (node (ref "JIN") (pin "33") (pinfunction "Z30_33") (pintype "passive"))
    )
    (net (code "143") (name "unconnected-(JIN-Z31-Pad34)") (class "Default")
      (node (ref "JIN") (pin "34") (pinfunction "Z31_34") (pintype "passive"))
    )
    (net (code "144") (name "unconnected-(JOUT-Pad21)") (class "Default")
      (node (ref "JOUT") (pin "21") (pinfunction "21_21") (pintype "passive"))
    )
    (net (code "145") (name "unconnected-(JOUT-Pad22)") (class "Default")
      (node (ref "JOUT") (pin "22") (pinfunction "22_22") (pintype "passive"))
    )
    (net (code "146") (name "unconnected-(JOUT-Pad23)") (class "Default")
      (node (ref "JOUT") (pin "23") (pinfunction "23_23") (pintype "passive"))
    )
    (net (code "147") (name "unconnected-(JOUT-Pad24)") (class "Default")
      (node (ref "JOUT") (pin "24") (pinfunction "24_24") (pintype "passive"))
    )
    (net (code "148") (name "unconnected-(JOUT-Pad25)") (class "Default")
      (node (ref "JOUT") (pin "25") (pinfunction "25_25") (pintype "passive"))
    )
    (net (code "149") (name "unconnected-(JRF7-Pad1)") (class "Default")
      (node (ref "JRF7") (pin "1") (pinfunction "1_1") (pintype "passive"))
    )
    (net (code "150") (name "unconnected-(JRF7-Pad2)") (class "Default")
      (node (ref "JRF7") (pin "2") (pinfunction "2_2") (pintype "passive"))
    )
    (net (code "151") (name "unconnected-(JRF7-Pad3)") (class "Default")
      (node (ref "JRF7") (pin "3") (pinfunction "3_3") (pintype "passive"))
    )
    (net (code "152") (name "unconnected-(JRF7-Pad4)") (class "Default")
      (node (ref "JRF7") (pin "4") (pinfunction "4_4") (pintype "passive"))
    )
    (net (code "153") (name "unconnected-(JRF7-Pad5)") (class "Default")
      (node (ref "JRF7") (pin "5") (pinfunction "5_5") (pintype "passive"))
    )
    (net (code "154") (name "unconnected-(T7-DC-Pad3)") (class "Default")
      (node (ref "T7") (pin "3") (pinfunction "DC_3") (pintype "input"))
    )
    (net (code "155") (name "unconnected-(T7-Pad1)") (class "Default")
      (node (ref "T7") (pin "1") (pinfunction "1_1") (pintype "passive"))
    )
    (net (code "156") (name "unconnected-(T7-Pad2)") (class "Default")
      (node (ref "T7") (pin "2") (pinfunction "2_2") (pintype "passive"))
    )
    (net (code "157") (name "unconnected-(T7-Pad4)") (class "Default")
      (node (ref "T7") (pin "4") (pinfunction "4_4") (pintype "passive"))
    )
    (net (code "158") (name "unconnected-(T7-Pad5)") (class "Default")
      (node (ref "T7") (pin "5") (pinfunction "5_5") (pintype "passive"))
    )
    (net (code "159") (name "unconnected-(T7-Pad6)") (class "Default")
      (node (ref "T7") (pin "6") (pinfunction "6_6") (pintype "passive"))
    )
    (net (code "160") (name "unconnected-(T7-Pad7)") (class "Default")
      (node (ref "T7") (pin "7") (pinfunction "7_7") (pintype "passive"))
    )
    (net (code "161") (name "unconnected-(T7-Pad8)") (class "Default")
      (node (ref "T7") (pin "8") (pinfunction "8_8") (pintype "passive"))
    )
    (net (code "162") (name "unconnected-(T7-Pad10)") (class "Default")
      (node (ref "T7") (pin "10") (pinfunction "10_10") (pintype "passive"))
    )
    (net (code "163") (name "unconnected-(T7-Pad11)") (class "Default")
      (node (ref "T7") (pin "11") (pinfunction "11_11") (pintype "passive"))
    )
    (net (code "164") (name "unconnected-(T7-Pad13)") (class "Default")
      (node (ref "T7") (pin "13") (pinfunction "13_13") (pintype "passive"))
    )
    (net (code "165") (name "unconnected-(T7-Pad14)") (class "Default")
      (node (ref "T7") (pin "14") (pinfunction "14_14") (pintype "passive"))
    )
    (net (code "166") (name "unconnected-(T7-Pad15)") (class "Default")
      (node (ref "T7") (pin "15") (pinfunction "15_15") (pintype "passive"))
    )
    (net (code "167") (name "unconnected-(T7-Pad16)") (class "Default")
      (node (ref "T7") (pin "16") (pinfunction "16_16") (pintype "passive"))
    )
    (net (code "168") (name "unconnected-(T7-RF+DC-Pad12)") (class "Default")
      (node (ref "T7") (pin "12") (pinfunction "RF+DC_12") (pintype "output"))
    )
    (net (code "169") (name "unconnected-(T7-RF-Pad9)") (class "Default")
      (node (ref "T7") (pin "9") (pinfunction "RF_9") (pintype "input"))
    )
    (net (code "170") (name "unconnected-(U1-EP-Pad9)") (class "Default")
      (node (ref "U1") (pin "9") (pinfunction "EP_9") (pintype "power_in"))
    )
    (net (code "171") (name "unconnected-(U1-E{slash}D-Pad8)") (class "Default")
      (node (ref "U1") (pin "8") (pinfunction "E/D_8") (pintype "input"))
    )
    (net (code "172") (name "unconnected-(U1-E{slash}D_COM-Pad1)") (class "Default")
      (node (ref "U1") (pin "1") (pinfunction "E/D_COM_1") (pintype "power_in"))
    )
    (net (code "173") (name "unconnected-(U1-STATUS_FLAG-Pad5)") (class "Default")
      (node (ref "U1") (pin "5") (pinfunction "STATUS_FLAG_5") (pintype "open_collector"))
    )
    (net (code "174") (name "unconnected-(U2-EP-Pad9)") (class "Default")
      (node (ref "U2") (pin "9") (pinfunction "EP_9") (pintype "power_in"))
    )
    (net (code "175") (name "unconnected-(U2-E{slash}D-Pad8)") (class "Default")
      (node (ref "U2") (pin "8") (pinfunction "E/D_8") (pintype "input"))
    )
    (net (code "176") (name "unconnected-(U2-E{slash}D_COM-Pad1)") (class "Default")
      (node (ref "U2") (pin "1") (pinfunction "E/D_COM_1") (pintype "power_in"))
    )
    (net (code "177") (name "unconnected-(U2-STATUS_FLAG-Pad5)") (class "Default")
      (node (ref "U2") (pin "5") (pinfunction "STATUS_FLAG_5") (pintype "open_collector"))
    )
    (net (code "178") (name "unconnected-(U3-EP-Pad9)") (class "Default")
      (node (ref "U3") (pin "9") (pinfunction "EP_9") (pintype "power_in"))
    )
    (net (code "179") (name "unconnected-(U3-E{slash}D-Pad8)") (class "Default")
      (node (ref "U3") (pin "8") (pinfunction "E/D_8") (pintype "input"))
    )
    (net (code "180") (name "unconnected-(U3-E{slash}D_COM-Pad1)") (class "Default")
      (node (ref "U3") (pin "1") (pinfunction "E/D_COM_1") (pintype "power_in"))
    )
    (net (code "181") (name "unconnected-(U3-STATUS_FLAG-Pad5)") (class "Default")
      (node (ref "U3") (pin "5") (pinfunction "STATUS_FLAG_5") (pintype "open_collector"))
    )
    (net (code "182") (name "unconnected-(U4-EP-Pad9)") (class "Default")
      (node (ref "U4") (pin "9") (pinfunction "EP_9") (pintype "power_in"))
    )
    (net (code "183") (name "unconnected-(U4-E{slash}D-Pad8)") (class "Default")
      (node (ref "U4") (pin "8") (pinfunction "E/D_8") (pintype "input"))
    )
    (net (code "184") (name "unconnected-(U4-E{slash}D_COM-Pad1)") (class "Default")
      (node (ref "U4") (pin "1") (pinfunction "E/D_COM_1") (pintype "power_in"))
    )
    (net (code "185") (name "unconnected-(U4-STATUS_FLAG-Pad5)") (class "Default")
      (node (ref "U4") (pin "5") (pinfunction "STATUS_FLAG_5") (pintype "open_collector"))
    )
    (net (code "186") (name "unconnected-(U5-EP-Pad9)") (class "Default")
      (node (ref "U5") (pin "9") (pinfunction "EP_9") (pintype "power_in"))
    )
    (net (code "187") (name "unconnected-(U5-E{slash}D-Pad8)") (class "Default")
      (node (ref "U5") (pin "8") (pinfunction "E/D_8") (pintype "input"))
    )
    (net (code "188") (name "unconnected-(U5-E{slash}D_COM-Pad1)") (class "Default")
      (node (ref "U5") (pin "1") (pinfunction "E/D_COM_1") (pintype "power_in"))
    )
    (net (code "189") (name "unconnected-(U5-STATUS_FLAG-Pad5)") (class "Default")
      (node (ref "U5") (pin "5") (pinfunction "STATUS_FLAG_5") (pintype "open_collector"))
    )
    (net (code "190") (name "unconnected-(U6-EP-Pad9)") (class "Default")
      (node (ref "U6") (pin "9") (pinfunction "EP_9") (pintype "power_in"))
    )
    (net (code "191") (name "unconnected-(U6-E{slash}D-Pad8)") (class "Default")
      (node (ref "U6") (pin "8") (pinfunction "E/D_8") (pintype "input"))
    )
    (net (code "192") (name "unconnected-(U6-E{slash}D_COM-Pad1)") (class "Default")
      (node (ref "U6") (pin "1") (pinfunction "E/D_COM_1") (pintype "power_in"))
    )
    (net (code "193") (name "unconnected-(U6-STATUS_FLAG-Pad5)") (class "Default")
      (node (ref "U6") (pin "5") (pinfunction "STATUS_FLAG_5") (pintype "open_collector"))
    )
    (net (code "194") (name "unconnected-(U7-EP-Pad9)") (class "Default")
      (node (ref "U7") (pin "9") (pinfunction "EP_9") (pintype "power_in"))
    )
    (net (code "195") (name "unconnected-(U7-E{slash}D-Pad8)") (class "Default")
      (node (ref "U7") (pin "8") (pinfunction "E/D_8") (pintype "input"))
    )
    (net (code "196") (name "unconnected-(U7-E{slash}D_COM-Pad1)") (class "Default")
      (node (ref "U7") (pin "1") (pinfunction "E/D_COM_1") (pintype "power_in"))
    )
    (net (code "197") (name "unconnected-(U7-STATUS_FLAG-Pad5)") (class "Default")
      (node (ref "U7") (pin "5") (pinfunction "STATUS_FLAG_5") (pintype "open_collector"))
    )
    (net (code "198") (name "unconnected-(U8-EP-Pad9)") (class "Default")
      (node (ref "U8") (pin "9") (pinfunction "EP_9") (pintype "power_in"))
    )
    (net (code "199") (name "unconnected-(U8-E{slash}D-Pad8)") (class "Default")
      (node (ref "U8") (pin "8") (pinfunction "E/D_8") (pintype "input"))
    )
    (net (code "200") (name "unconnected-(U8-E{slash}D_COM-Pad1)") (class "Default")
      (node (ref "U8") (pin "1") (pinfunction "E/D_COM_1") (pintype "power_in"))
    )
    (net (code "201") (name "unconnected-(U8-STATUS_FLAG-Pad5)") (class "Default")
      (node (ref "U8") (pin "5") (pinfunction "STATUS_FLAG_5") (pintype "open_collector"))
    )
    (net (code "202") (name "unconnected-(U9-EP-Pad9)") (class "Default")
      (node (ref "U9") (pin "9") (pinfunction "EP_9") (pintype "power_in"))
    )
    (net (code "203") (name "unconnected-(U9-E{slash}D-Pad8)") (class "Default")
      (node (ref "U9") (pin "8") (pinfunction "E/D_8") (pintype "input"))
    )
    (net (code "204") (name "unconnected-(U9-E{slash}D_COM-Pad1)") (class "Default")
      (node (ref "U9") (pin "1") (pinfunction "E/D_COM_1") (pintype "power_in"))
    )
    (net (code "205") (name "unconnected-(U9-STATUS_FLAG-Pad5)") (class "Default")
      (node (ref "U9") (pin "5") (pinfunction "STATUS_FLAG_5") (pintype "open_collector"))
    )
    (net (code "206") (name "unconnected-(U10-EP-Pad9)") (class "Default")
      (node (ref "U10") (pin "9") (pinfunction "EP_9") (pintype "power_in"))
    )
    (net (code "207") (name "unconnected-(U10-E{slash}D-Pad8)") (class "Default")
      (node (ref "U10") (pin "8") (pinfunction "E/D_8") (pintype "input"))
    )
    (net (code "208") (name "unconnected-(U10-E{slash}D_COM-Pad1)") (class "Default")
      (node (ref "U10") (pin "1") (pinfunction "E/D_COM_1") (pintype "power_in"))
    )
    (net (code "209") (name "unconnected-(U10-STATUS_FLAG-Pad5)") (class "Default")
      (node (ref "U10") (pin "5") (pinfunction "STATUS_FLAG_5") (pintype "open_collector"))
    )
    (net (code "210") (name "unconnected-(U11-EP-Pad9)") (class "Default")
      (node (ref "U11") (pin "9") (pinfunction "EP_9") (pintype "power_in"))
    )
    (net (code "211") (name "unconnected-(U11-E{slash}D-Pad8)") (class "Default")
      (node (ref "U11") (pin "8") (pinfunction "E/D_8") (pintype "input"))
    )
    (net (code "212") (name "unconnected-(U11-E{slash}D_COM-Pad1)") (class "Default")
      (node (ref "U11") (pin "1") (pinfunction "E/D_COM_1") (pintype "power_in"))
    )
    (net (code "213") (name "unconnected-(U11-STATUS_FLAG-Pad5)") (class "Default")
      (node (ref "U11") (pin "5") (pinfunction "STATUS_FLAG_5") (pintype "open_collector"))
    )
    (net (code "214") (name "unconnected-(U12-EP-Pad9)") (class "Default")
      (node (ref "U12") (pin "9") (pinfunction "EP_9") (pintype "power_in"))
    )
    (net (code "215") (name "unconnected-(U12-E{slash}D-Pad8)") (class "Default")
      (node (ref "U12") (pin "8") (pinfunction "E/D_8") (pintype "input"))
    )
    (net (code "216") (name "unconnected-(U12-E{slash}D_COM-Pad1)") (class "Default")
      (node (ref "U12") (pin "1") (pinfunction "E/D_COM_1") (pintype "power_in"))
    )
    (net (code "217") (name "unconnected-(U12-STATUS_FLAG-Pad5)") (class "Default")
      (node (ref "U12") (pin "5") (pinfunction "STATUS_FLAG_5") (pintype "open_collector"))
    )
    (net (code "218") (name "unconnected-(U13-EP-Pad9)") (class "Default")
      (node (ref "U13") (pin "9") (pinfunction "EP_9") (pintype "power_in"))
    )
    (net (code "219") (name "unconnected-(U13-E{slash}D-Pad8)") (class "Default")
      (node (ref "U13") (pin "8") (pinfunction "E/D_8") (pintype "input"))
    )
    (net (code "220") (name "unconnected-(U13-E{slash}D_COM-Pad1)") (class "Default")
      (node (ref "U13") (pin "1") (pinfunction "E/D_COM_1") (pintype "power_in"))
    )
    (net (code "221") (name "unconnected-(U13-STATUS_FLAG-Pad5)") (class "Default")
      (node (ref "U13") (pin "5") (pinfunction "STATUS_FLAG_5") (pintype "open_collector"))
    )
    (net (code "222") (name "unconnected-(U14-EP-Pad9)") (class "Default")
      (node (ref "U14") (pin "9") (pinfunction "EP_9") (pintype "power_in"))
    )
    (net (code "223") (name "unconnected-(U14-E{slash}D-Pad8)") (class "Default")
      (node (ref "U14") (pin "8") (pinfunction "E/D_8") (pintype "input"))
    )
    (net (code "224") (name "unconnected-(U14-E{slash}D_COM-Pad1)") (class "Default")
      (node (ref "U14") (pin "1") (pinfunction "E/D_COM_1") (pintype "power_in"))
    )
    (net (code "225") (name "unconnected-(U14-STATUS_FLAG-Pad5)") (class "Default")
      (node (ref "U14") (pin "5") (pinfunction "STATUS_FLAG_5") (pintype "open_collector"))
    )
    (net (code "226") (name "unconnected-(U15-EP-Pad9)") (class "Default")
      (node (ref "U15") (pin "9") (pinfunction "EP_9") (pintype "power_in"))
    )
    (net (code "227") (name "unconnected-(U15-E{slash}D-Pad8)") (class "Default")
      (node (ref "U15") (pin "8") (pinfunction "E/D_8") (pintype "input"))
    )
    (net (code "228") (name "unconnected-(U15-E{slash}D_COM-Pad1)") (class "Default")
      (node (ref "U15") (pin "1") (pinfunction "E/D_COM_1") (pintype "power_in"))
    )
    (net (code "229") (name "unconnected-(U15-STATUS_FLAG-Pad5)") (class "Default")
      (node (ref "U15") (pin "5") (pinfunction "STATUS_FLAG_5") (pintype "open_collector"))
    )
    (net (code "230") (name "unconnected-(U16-EP-Pad9)") (class "Default")
      (node (ref "U16") (pin "9") (pinfunction "EP_9") (pintype "power_in"))
    )
    (net (code "231") (name "unconnected-(U16-E{slash}D-Pad8)") (class "Default")
      (node (ref "U16") (pin "8") (pinfunction "E/D_8") (pintype "input"))
    )
    (net (code "232") (name "unconnected-(U16-E{slash}D_COM-Pad1)") (class "Default")
      (node (ref "U16") (pin "1") (pinfunction "E/D_COM_1") (pintype "power_in"))
    )
    (net (code "233") (name "unconnected-(U16-STATUS_FLAG-Pad5)") (class "Default")
      (node (ref "U16") (pin "5") (pinfunction "STATUS_FLAG_5") (pintype "open_collector"))
    )
    (net (code "234") (name "unconnected-(U17-EP-Pad9)") (class "Default")
      (node (ref "U17") (pin "9") (pinfunction "EP_9") (pintype "power_in"))
    )
    (net (code "235") (name "unconnected-(U17-E{slash}D-Pad8)") (class "Default")
      (node (ref "U17") (pin "8") (pinfunction "E/D_8") (pintype "input"))
    )
    (net (code "236") (name "unconnected-(U17-E{slash}D_COM-Pad1)") (class "Default")
      (node (ref "U17") (pin "1") (pinfunction "E/D_COM_1") (pintype "power_in"))
    )
    (net (code "237") (name "unconnected-(U17-STATUS_FLAG-Pad5)") (class "Default")
      (node (ref "U17") (pin "5") (pinfunction "STATUS_FLAG_5") (pintype "open_collector"))
    )
    (net (code "238") (name "unconnected-(U18-EP-Pad9)") (class "Default")
      (node (ref "U18") (pin "9") (pinfunction "EP_9") (pintype "power_in"))
    )
    (net (code "239") (name "unconnected-(U18-E{slash}D-Pad8)") (class "Default")
      (node (ref "U18") (pin "8") (pinfunction "E/D_8") (pintype "input"))
    )
    (net (code "240") (name "unconnected-(U18-E{slash}D_COM-Pad1)") (class "Default")
      (node (ref "U18") (pin "1") (pinfunction "E/D_COM_1") (pintype "power_in"))
    )
    (net (code "241") (name "unconnected-(U18-STATUS_FLAG-Pad5)") (class "Default")
      (node (ref "U18") (pin "5") (pinfunction "STATUS_FLAG_5") (pintype "open_collector"))
    )
    (net (code "242") (name "unconnected-(U19-EP-Pad9)") (class "Default")
      (node (ref "U19") (pin "9") (pinfunction "EP_9") (pintype "power_in"))
    )
    (net (code "243") (name "unconnected-(U19-E{slash}D-Pad8)") (class "Default")
      (node (ref "U19") (pin "8") (pinfunction "E/D_8") (pintype "input"))
    )
    (net (code "244") (name "unconnected-(U19-E{slash}D_COM-Pad1)") (class "Default")
      (node (ref "U19") (pin "1") (pinfunction "E/D_COM_1") (pintype "power_in"))
    )
    (net (code "245") (name "unconnected-(U19-STATUS_FLAG-Pad5)") (class "Default")
      (node (ref "U19") (pin "5") (pinfunction "STATUS_FLAG_5") (pintype "open_collector"))
    )
    (net (code "246") (name "unconnected-(U20-EP-Pad9)") (class "Default")
      (node (ref "U20") (pin "9") (pinfunction "EP_9") (pintype "power_in"))
    )
    (net (code "247") (name "unconnected-(U20-E{slash}D-Pad8)") (class "Default")
      (node (ref "U20") (pin "8") (pinfunction "E/D_8") (pintype "input"))
    )
    (net (code "248") (name "unconnected-(U20-E{slash}D_COM-Pad1)") (class "Default")
      (node (ref "U20") (pin "1") (pinfunction "E/D_COM_1") (pintype "power_in"))
    )
    (net (code "249") (name "unconnected-(U20-STATUS_FLAG-Pad5)") (class "Default")
      (node (ref "U20") (pin "5") (pinfunction "STATUS_FLAG_5") (pintype "open_collector"))
    )
  )
)
